# experimentboard.net
KiCad netlist of a schematic drawn in EAGLE
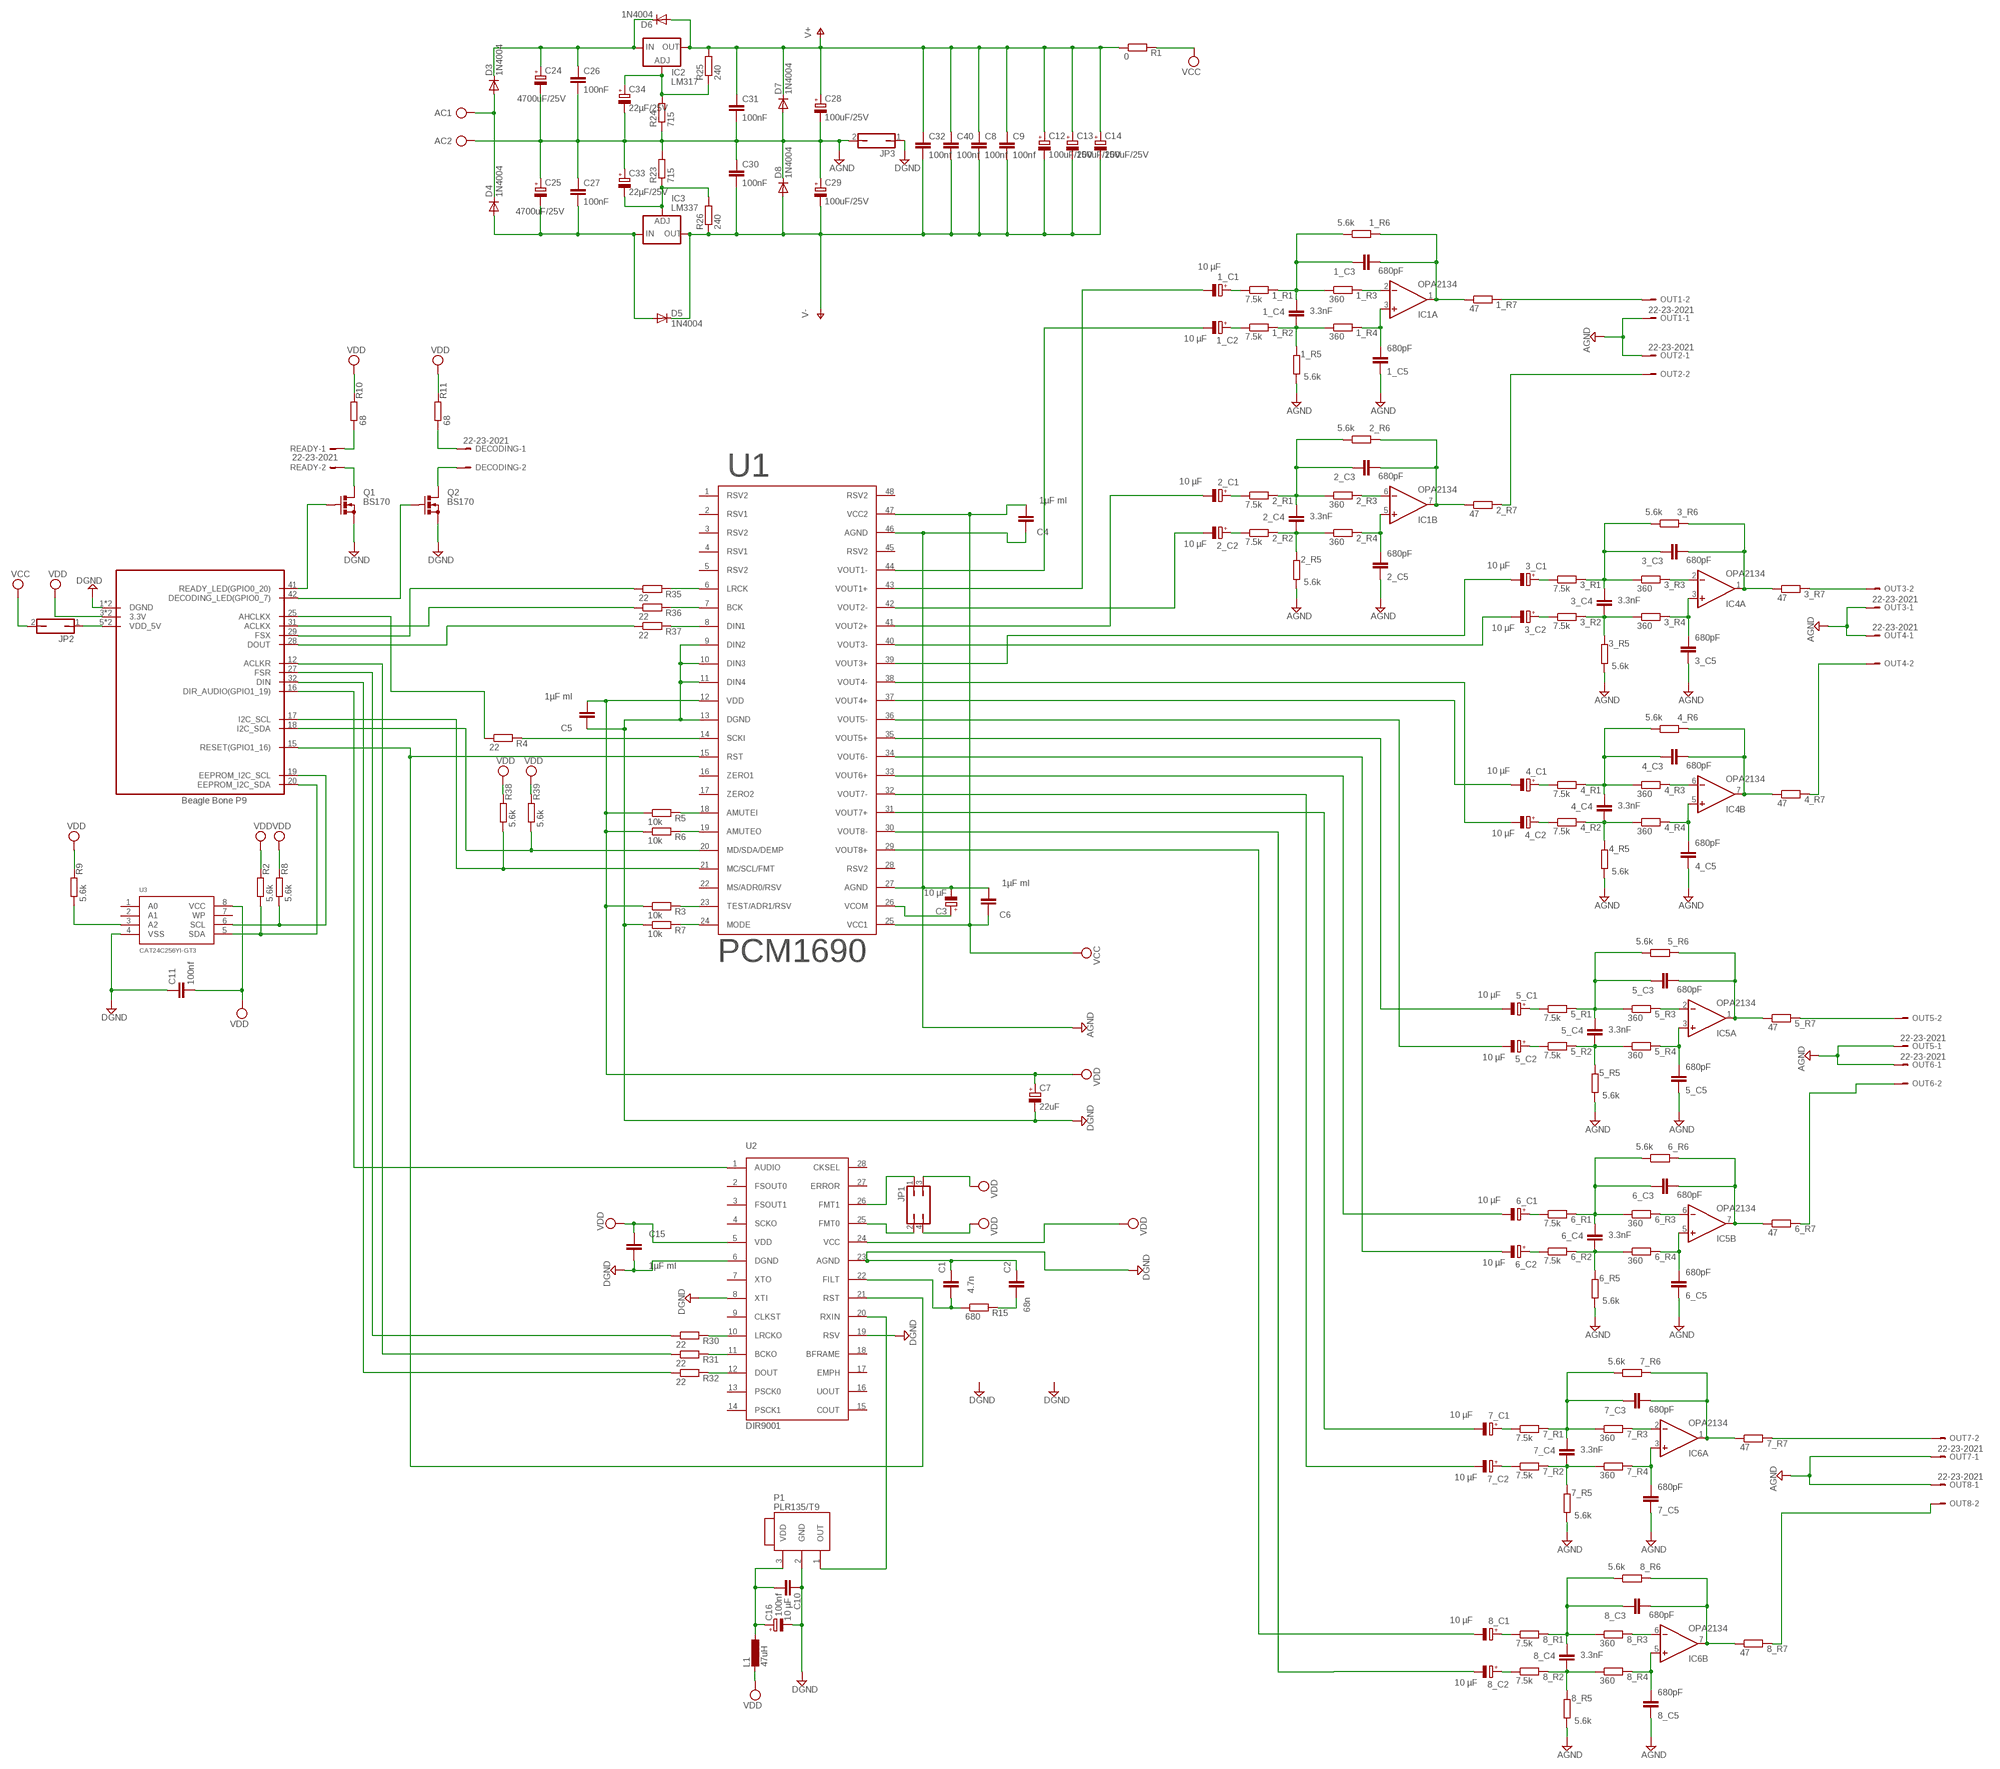
[diagram p0: schematic, sheet 1]

(export (version "E")
  (design (tool "Eeschema 10.0.6"))
  (components
    (comp (ref "1_C1")
      (value "10 µF")
      (footprint "eagle-import:E2-5")
      (libsource (lib "eagle-import") (part "CPOL-EUE2-5"))
    )
    (comp (ref "1_C2")
      (value "10 µF")
      (footprint "eagle-import:E2-5")
      (libsource (lib "eagle-import") (part "CPOL-EUE2-5"))
    )
    (comp (ref "1_C3")
      (value "680pF")
      (footprint "eagle-import:C050-024X044")
      (libsource (lib "eagle-import") (part "C-EU050-024X044"))
    )
    (comp (ref "1_C4")
      (value "3.3nF")
      (footprint "eagle-import:C050-025X075")
      (libsource (lib "eagle-import") (part "C-EU050-025X075"))
    )
    (comp (ref "1_C5")
      (value "680pF")
      (footprint "eagle-import:C050-024X044")
      (libsource (lib "eagle-import") (part "C-EU050-024X044"))
    )
    (comp (ref "1_R1")
      (value "7.5k")
      (footprint "eagle-import:0207_7")
      (libsource (lib "eagle-import") (part "R-EU_0207/7"))
    )
    (comp (ref "1_R2")
      (value "7.5k")
      (footprint "eagle-import:0207_7")
      (libsource (lib "eagle-import") (part "R-EU_0207/7"))
    )
    (comp (ref "1_R3")
      (value "360")
      (footprint "eagle-import:0207_7")
      (libsource (lib "eagle-import") (part "R-EU_0207/7"))
    )
    (comp (ref "1_R4")
      (value "360")
      (footprint "eagle-import:0207_7")
      (libsource (lib "eagle-import") (part "R-EU_0207/7"))
    )
    (comp (ref "1_R5")
      (value "5.6k")
      (footprint "eagle-import:0207_7")
      (libsource (lib "eagle-import") (part "R-EU_0207/7"))
    )
    (comp (ref "1_R6")
      (value "5.6k")
      (footprint "eagle-import:0207_7")
      (libsource (lib "eagle-import") (part "R-EU_0207/7"))
    )
    (comp (ref "1_R7")
      (value "47")
      (footprint "eagle-import:0207_7")
      (libsource (lib "eagle-import") (part "R-EU_0207/7"))
    )
    (comp (ref "2_C1")
      (value "10 µF")
      (footprint "eagle-import:E2-5")
      (libsource (lib "eagle-import") (part "CPOL-EUE2-5"))
    )
    (comp (ref "2_C2")
      (value "10 µF")
      (footprint "eagle-import:E2-5")
      (libsource (lib "eagle-import") (part "CPOL-EUE2-5"))
    )
    (comp (ref "2_C3")
      (value "680pF")
      (footprint "eagle-import:C050-024X044")
      (libsource (lib "eagle-import") (part "C-EU050-024X044"))
    )
    (comp (ref "2_C4")
      (value "3.3nF")
      (footprint "eagle-import:C050-025X075")
      (libsource (lib "eagle-import") (part "C-EU050-025X075"))
    )
    (comp (ref "2_C5")
      (value "680pF")
      (footprint "eagle-import:C050-024X044")
      (libsource (lib "eagle-import") (part "C-EU050-024X044"))
    )
    (comp (ref "2_R1")
      (value "7.5k")
      (footprint "eagle-import:0207_7")
      (libsource (lib "eagle-import") (part "R-EU_0207/7"))
    )
    (comp (ref "2_R2")
      (value "7.5k")
      (footprint "eagle-import:0207_7")
      (libsource (lib "eagle-import") (part "R-EU_0207/7"))
    )
    (comp (ref "2_R3")
      (value "360")
      (footprint "eagle-import:0207_7")
      (libsource (lib "eagle-import") (part "R-EU_0207/7"))
    )
    (comp (ref "2_R4")
      (value "360")
      (footprint "eagle-import:0207_7")
      (libsource (lib "eagle-import") (part "R-EU_0207/7"))
    )
    (comp (ref "2_R5")
      (value "5.6k")
      (footprint "eagle-import:0207_7")
      (libsource (lib "eagle-import") (part "R-EU_0207/7"))
    )
    (comp (ref "2_R6")
      (value "5.6k")
      (footprint "eagle-import:0207_7")
      (libsource (lib "eagle-import") (part "R-EU_0207/7"))
    )
    (comp (ref "2_R7")
      (value "47")
      (footprint "eagle-import:0207_7")
      (libsource (lib "eagle-import") (part "R-EU_0207/7"))
    )
    (comp (ref "3_C1")
      (value "10 µF")
      (footprint "eagle-import:E2-5")
      (libsource (lib "eagle-import") (part "CPOL-EUE2-5"))
    )
    (comp (ref "3_C2")
      (value "10 µF")
      (footprint "eagle-import:E2-5")
      (libsource (lib "eagle-import") (part "CPOL-EUE2-5"))
    )
    (comp (ref "3_C3")
      (value "680pF")
      (footprint "eagle-import:C050-024X044")
      (libsource (lib "eagle-import") (part "C-EU050-024X044"))
    )
    (comp (ref "3_C4")
      (value "3.3nF")
      (footprint "eagle-import:C050-025X075")
      (libsource (lib "eagle-import") (part "C-EU050-025X075"))
    )
    (comp (ref "3_C5")
      (value "680pF")
      (footprint "eagle-import:C050-024X044")
      (libsource (lib "eagle-import") (part "C-EU050-024X044"))
    )
    (comp (ref "3_R1")
      (value "7.5k")
      (footprint "eagle-import:0207_7")
      (libsource (lib "eagle-import") (part "R-EU_0207/7"))
    )
    (comp (ref "3_R2")
      (value "7.5k")
      (footprint "eagle-import:0207_7")
      (libsource (lib "eagle-import") (part "R-EU_0207/7"))
    )
    (comp (ref "3_R3")
      (value "360")
      (footprint "eagle-import:0207_7")
      (libsource (lib "eagle-import") (part "R-EU_0207/7"))
    )
    (comp (ref "3_R4")
      (value "360")
      (footprint "eagle-import:0207_7")
      (libsource (lib "eagle-import") (part "R-EU_0207/7"))
    )
    (comp (ref "3_R5")
      (value "5.6k")
      (footprint "eagle-import:0207_7")
      (libsource (lib "eagle-import") (part "R-EU_0207/7"))
    )
    (comp (ref "3_R6")
      (value "5.6k")
      (footprint "eagle-import:0207_7")
      (libsource (lib "eagle-import") (part "R-EU_0207/7"))
    )
    (comp (ref "3_R7")
      (value "47")
      (footprint "eagle-import:0207_7")
      (libsource (lib "eagle-import") (part "R-EU_0207/7"))
    )
    (comp (ref "4_C1")
      (value "10 µF")
      (footprint "eagle-import:E2-5")
      (libsource (lib "eagle-import") (part "CPOL-EUE2-5"))
    )
    (comp (ref "4_C2")
      (value "10 µF")
      (footprint "eagle-import:E2-5")
      (libsource (lib "eagle-import") (part "CPOL-EUE2-5"))
    )
    (comp (ref "4_C3")
      (value "680pF")
      (footprint "eagle-import:C050-024X044")
      (libsource (lib "eagle-import") (part "C-EU050-024X044"))
    )
    (comp (ref "4_C4")
      (value "3.3nF")
      (footprint "eagle-import:C050-025X075")
      (libsource (lib "eagle-import") (part "C-EU050-025X075"))
    )
    (comp (ref "4_C5")
      (value "680pF")
      (footprint "eagle-import:C050-024X044")
      (libsource (lib "eagle-import") (part "C-EU050-024X044"))
    )
    (comp (ref "4_R1")
      (value "7.5k")
      (footprint "eagle-import:0207_7")
      (libsource (lib "eagle-import") (part "R-EU_0207/7"))
    )
    (comp (ref "4_R2")
      (value "7.5k")
      (footprint "eagle-import:0207_7")
      (libsource (lib "eagle-import") (part "R-EU_0207/7"))
    )
    (comp (ref "4_R3")
      (value "360")
      (footprint "eagle-import:0207_7")
      (libsource (lib "eagle-import") (part "R-EU_0207/7"))
    )
    (comp (ref "4_R4")
      (value "360")
      (footprint "eagle-import:0207_7")
      (libsource (lib "eagle-import") (part "R-EU_0207/7"))
    )
    (comp (ref "4_R5")
      (value "5.6k")
      (footprint "eagle-import:0207_7")
      (libsource (lib "eagle-import") (part "R-EU_0207/7"))
    )
    (comp (ref "4_R6")
      (value "5.6k")
      (footprint "eagle-import:0207_7")
      (libsource (lib "eagle-import") (part "R-EU_0207/7"))
    )
    (comp (ref "4_R7")
      (value "47")
      (footprint "eagle-import:0207_7")
      (libsource (lib "eagle-import") (part "R-EU_0207/7"))
    )
    (comp (ref "5_C1")
      (value "10 µF")
      (footprint "eagle-import:E2-5")
      (libsource (lib "eagle-import") (part "CPOL-EUE2-5"))
    )
    (comp (ref "5_C2")
      (value "10 µF")
      (footprint "eagle-import:E2-5")
      (libsource (lib "eagle-import") (part "CPOL-EUE2-5"))
    )
    (comp (ref "5_C3")
      (value "680pF")
      (footprint "eagle-import:C050-024X044")
      (libsource (lib "eagle-import") (part "C-EU050-024X044"))
    )
    (comp (ref "5_C4")
      (value "3.3nF")
      (footprint "eagle-import:C050-025X075")
      (libsource (lib "eagle-import") (part "C-EU050-025X075"))
    )
    (comp (ref "5_C5")
      (value "680pF")
      (footprint "eagle-import:C050-024X044")
      (libsource (lib "eagle-import") (part "C-EU050-024X044"))
    )
    (comp (ref "5_R1")
      (value "7.5k")
      (footprint "eagle-import:0207_7")
      (libsource (lib "eagle-import") (part "R-EU_0207/7"))
    )
    (comp (ref "5_R2")
      (value "7.5k")
      (footprint "eagle-import:0207_7")
      (libsource (lib "eagle-import") (part "R-EU_0207/7"))
    )
    (comp (ref "5_R3")
      (value "360")
      (footprint "eagle-import:0207_7")
      (libsource (lib "eagle-import") (part "R-EU_0207/7"))
    )
    (comp (ref "5_R4")
      (value "360")
      (footprint "eagle-import:0207_7")
      (libsource (lib "eagle-import") (part "R-EU_0207/7"))
    )
    (comp (ref "5_R5")
      (value "5.6k")
      (footprint "eagle-import:0207_7")
      (libsource (lib "eagle-import") (part "R-EU_0207/7"))
    )
    (comp (ref "5_R6")
      (value "5.6k")
      (footprint "eagle-import:0207_7")
      (libsource (lib "eagle-import") (part "R-EU_0207/7"))
    )
    (comp (ref "5_R7")
      (value "47")
      (footprint "eagle-import:0207_7")
      (libsource (lib "eagle-import") (part "R-EU_0207/7"))
    )
    (comp (ref "6_C1")
      (value "10 µF")
      (footprint "eagle-import:E2-5")
      (libsource (lib "eagle-import") (part "CPOL-EUE2-5"))
    )
    (comp (ref "6_C2")
      (value "10 µF")
      (footprint "eagle-import:E2-5")
      (libsource (lib "eagle-import") (part "CPOL-EUE2-5"))
    )
    (comp (ref "6_C3")
      (value "680pF")
      (footprint "eagle-import:C050-024X044")
      (libsource (lib "eagle-import") (part "C-EU050-024X044"))
    )
    (comp (ref "6_C4")
      (value "3.3nF")
      (footprint "eagle-import:C050-025X075")
      (libsource (lib "eagle-import") (part "C-EU050-025X075"))
    )
    (comp (ref "6_C5")
      (value "680pF")
      (footprint "eagle-import:C050-024X044")
      (libsource (lib "eagle-import") (part "C-EU050-024X044"))
    )
    (comp (ref "6_R1")
      (value "7.5k")
      (footprint "eagle-import:0207_7")
      (libsource (lib "eagle-import") (part "R-EU_0207/7"))
    )
    (comp (ref "6_R2")
      (value "7.5k")
      (footprint "eagle-import:0207_7")
      (libsource (lib "eagle-import") (part "R-EU_0207/7"))
    )
    (comp (ref "6_R3")
      (value "360")
      (footprint "eagle-import:0207_7")
      (libsource (lib "eagle-import") (part "R-EU_0207/7"))
    )
    (comp (ref "6_R4")
      (value "360")
      (footprint "eagle-import:0207_7")
      (libsource (lib "eagle-import") (part "R-EU_0207/7"))
    )
    (comp (ref "6_R5")
      (value "5.6k")
      (footprint "eagle-import:0207_7")
      (libsource (lib "eagle-import") (part "R-EU_0207/7"))
    )
    (comp (ref "6_R6")
      (value "5.6k")
      (footprint "eagle-import:0207_7")
      (libsource (lib "eagle-import") (part "R-EU_0207/7"))
    )
    (comp (ref "6_R7")
      (value "47")
      (footprint "eagle-import:0207_7")
      (libsource (lib "eagle-import") (part "R-EU_0207/7"))
    )
    (comp (ref "7_C1")
      (value "10 µF")
      (footprint "eagle-import:E2-5")
      (libsource (lib "eagle-import") (part "CPOL-EUE2-5"))
    )
    (comp (ref "7_C2")
      (value "10 µF")
      (footprint "eagle-import:E2-5")
      (libsource (lib "eagle-import") (part "CPOL-EUE2-5"))
    )
    (comp (ref "7_C3")
      (value "680pF")
      (footprint "eagle-import:C050-024X044")
      (libsource (lib "eagle-import") (part "C-EU050-024X044"))
    )
    (comp (ref "7_C4")
      (value "3.3nF")
      (footprint "eagle-import:C050-025X075")
      (libsource (lib "eagle-import") (part "C-EU050-025X075"))
    )
    (comp (ref "7_C5")
      (value "680pF")
      (footprint "eagle-import:C050-024X044")
      (libsource (lib "eagle-import") (part "C-EU050-024X044"))
    )
    (comp (ref "7_R1")
      (value "7.5k")
      (footprint "eagle-import:0207_7")
      (libsource (lib "eagle-import") (part "R-EU_0207/7"))
    )
    (comp (ref "7_R2")
      (value "7.5k")
      (footprint "eagle-import:0207_7")
      (libsource (lib "eagle-import") (part "R-EU_0207/7"))
    )
    (comp (ref "7_R3")
      (value "360")
      (footprint "eagle-import:0207_7")
      (libsource (lib "eagle-import") (part "R-EU_0207/7"))
    )
    (comp (ref "7_R4")
      (value "360")
      (footprint "eagle-import:0207_7")
      (libsource (lib "eagle-import") (part "R-EU_0207/7"))
    )
    (comp (ref "7_R5")
      (value "5.6k")
      (footprint "eagle-import:0207_7")
      (libsource (lib "eagle-import") (part "R-EU_0207/7"))
    )
    (comp (ref "7_R6")
      (value "5.6k")
      (footprint "eagle-import:0207_7")
      (libsource (lib "eagle-import") (part "R-EU_0207/7"))
    )
    (comp (ref "7_R7")
      (value "47")
      (footprint "eagle-import:0207_7")
      (libsource (lib "eagle-import") (part "R-EU_0207/7"))
    )
    (comp (ref "8_C1")
      (value "10 µF")
      (footprint "eagle-import:E2-5")
      (libsource (lib "eagle-import") (part "CPOL-EUE2-5"))
    )
    (comp (ref "8_C2")
      (value "10 µF")
      (footprint "eagle-import:E2-5")
      (libsource (lib "eagle-import") (part "CPOL-EUE2-5"))
    )
    (comp (ref "8_C3")
      (value "680pF")
      (footprint "eagle-import:C050-024X044")
      (libsource (lib "eagle-import") (part "C-EU050-024X044"))
    )
    (comp (ref "8_C4")
      (value "3.3nF")
      (footprint "eagle-import:C050-025X075")
      (libsource (lib "eagle-import") (part "C-EU050-025X075"))
    )
    (comp (ref "8_C5")
      (value "680pF")
      (footprint "eagle-import:C050-024X044")
      (libsource (lib "eagle-import") (part "C-EU050-024X044"))
    )
    (comp (ref "8_R1")
      (value "7.5k")
      (footprint "eagle-import:0207_7")
      (libsource (lib "eagle-import") (part "R-EU_0207/7"))
    )
    (comp (ref "8_R2")
      (value "7.5k")
      (footprint "eagle-import:0207_7")
      (libsource (lib "eagle-import") (part "R-EU_0207/7"))
    )
    (comp (ref "8_R3")
      (value "360")
      (footprint "eagle-import:0207_7")
      (libsource (lib "eagle-import") (part "R-EU_0207/7"))
    )
    (comp (ref "8_R4")
      (value "360")
      (footprint "eagle-import:0207_7")
      (libsource (lib "eagle-import") (part "R-EU_0207/7"))
    )
    (comp (ref "8_R5")
      (value "5.6k")
      (footprint "eagle-import:0207_7")
      (libsource (lib "eagle-import") (part "R-EU_0207/7"))
    )
    (comp (ref "8_R6")
      (value "5.6k")
      (footprint "eagle-import:0207_7")
      (libsource (lib "eagle-import") (part "R-EU_0207/7"))
    )
    (comp (ref "8_R7")
      (value "47")
      (footprint "eagle-import:0207_7")
      (libsource (lib "eagle-import") (part "R-EU_0207/7"))
    )
    (comp (ref "AC")
      (value "ADAPTER-PLUG-5.5MM")
      (footprint "eagle-import:ADAPTER-PLUG-5.5MM")
      (libsource (lib "eagle-import") (part "ADAPTER-PLUG-5.5MM"))
    )
    (comp (ref "C1")
      (value "4.7n")
      (footprint "eagle-import:C050-024X044")
      (libsource (lib "eagle-import") (part "C-EU050-024X044"))
    )
    (comp (ref "C2")
      (value "68n")
      (footprint "eagle-import:C050-024X044")
      (libsource (lib "eagle-import") (part "C-EU050-024X044"))
    )
    (comp (ref "C3")
      (value "10 µF")
      (footprint "eagle-import:E2-5")
      (libsource (lib "eagle-import") (part "CPOL-EUE2-5"))
    )
    (comp (ref "C4")
      (value "1µF ml")
      (footprint "eagle-import:C050-024X044")
      (libsource (lib "eagle-import") (part "C-EU050-024X044"))
    )
    (comp (ref "C5")
      (value "1µF ml")
      (footprint "eagle-import:C050-024X044")
      (libsource (lib "eagle-import") (part "C-EU050-024X044"))
    )
    (comp (ref "C6")
      (value "1µF ml")
      (footprint "eagle-import:C050-024X044")
      (libsource (lib "eagle-import") (part "C-EU050-024X044"))
    )
    (comp (ref "C7")
      (value "22uF")
      (footprint "eagle-import:E2-5")
      (libsource (lib "eagle-import") (part "CPOL-EUE2-5"))
    )
    (comp (ref "C8")
      (value "100nf")
      (footprint "eagle-import:C050-024X044")
      (libsource (lib "eagle-import") (part "C-EU050-024X044"))
    )
    (comp (ref "C9")
      (value "100nf")
      (footprint "eagle-import:C050-024X044")
      (libsource (lib "eagle-import") (part "C-EU050-024X044"))
    )
    (comp (ref "C10")
      (value "100nf")
      (footprint "eagle-import:C050-024X044")
      (libsource (lib "eagle-import") (part "C-EU050-024X044"))
    )
    (comp (ref "C11")
      (value "100nf")
      (footprint "eagle-import:C050-024X044")
      (libsource (lib "eagle-import") (part "C-EU050-024X044"))
    )
    (comp (ref "C12")
      (value "100uF/25V")
      (footprint "eagle-import:E2,5-6")
      (libsource (lib "eagle-import") (part "CPOL-EUE2.5-6"))
    )
    (comp (ref "C13")
      (value "100uF/25V")
      (footprint "eagle-import:E2,5-6")
      (libsource (lib "eagle-import") (part "CPOL-EUE2.5-6"))
    )
    (comp (ref "C14")
      (value "100uF/25V")
      (footprint "eagle-import:E2,5-6")
      (libsource (lib "eagle-import") (part "CPOL-EUE2.5-6"))
    )
    (comp (ref "C15")
      (value "1µF ml")
      (footprint "eagle-import:C050-024X044")
      (libsource (lib "eagle-import") (part "C-EU050-024X044"))
    )
    (comp (ref "C16")
      (value "10 µF")
      (footprint "eagle-import:E2-5")
      (libsource (lib "eagle-import") (part "CPOL-EUE2-5"))
    )
    (comp (ref "C24")
      (value "4700uF/25V")
      (footprint "eagle-import:E7,5-16")
      (libsource (lib "eagle-import") (part "CPOL-EUE7.5-16"))
    )
    (comp (ref "C25")
      (value "4700uF/25V")
      (footprint "eagle-import:E7,5-16")
      (libsource (lib "eagle-import") (part "CPOL-EUE7.5-16"))
    )
    (comp (ref "C26")
      (value "100nF")
      (footprint "eagle-import:C050-024X044")
      (libsource (lib "eagle-import") (part "C-EU050-024X044"))
    )
    (comp (ref "C27")
      (value "100nF")
      (footprint "eagle-import:C050-024X044")
      (libsource (lib "eagle-import") (part "C-EU050-024X044"))
    )
    (comp (ref "C28")
      (value "100uF/25V")
      (footprint "eagle-import:E2,5-6")
      (libsource (lib "eagle-import") (part "CPOL-EUE2.5-6"))
    )
    (comp (ref "C29")
      (value "100uF/25V")
      (footprint "eagle-import:E2,5-6")
      (libsource (lib "eagle-import") (part "CPOL-EUE2.5-6"))
    )
    (comp (ref "C30")
      (value "100nF")
      (footprint "eagle-import:C050-024X044")
      (libsource (lib "eagle-import") (part "C-EU050-024X044"))
    )
    (comp (ref "C31")
      (value "100nF")
      (footprint "eagle-import:C050-024X044")
      (libsource (lib "eagle-import") (part "C-EU050-024X044"))
    )
    (comp (ref "C32")
      (value "100nf")
      (footprint "eagle-import:C050-024X044")
      (libsource (lib "eagle-import") (part "C-EU050-024X044"))
    )
    (comp (ref "C33")
      (value "22µF/25V")
      (footprint "eagle-import:E2,5-6")
      (libsource (lib "eagle-import") (part "CPOL-EUE2.5-6"))
    )
    (comp (ref "C34")
      (value "22µF/25V")
      (footprint "eagle-import:E2,5-6")
      (libsource (lib "eagle-import") (part "CPOL-EUE2.5-6"))
    )
    (comp (ref "C40")
      (value "100nf")
      (footprint "eagle-import:C050-024X044")
      (libsource (lib "eagle-import") (part "C-EU050-024X044"))
    )
    (comp (ref "D3")
      (value "1N4004")
      (footprint "eagle-import:DO41-7.6")
      (libsource (lib "eagle-import") (part "DIODE-DO41-7.6"))
    )
    (comp (ref "D4")
      (value "1N4004")
      (footprint "eagle-import:DO41-7.6")
      (libsource (lib "eagle-import") (part "DIODE-DO41-7.6"))
    )
    (comp (ref "D5")
      (value "1N4004")
      (footprint "eagle-import:DO41-7.6")
      (libsource (lib "eagle-import") (part "DIODE-DO41-7.6"))
    )
    (comp (ref "D6")
      (value "1N4004")
      (footprint "eagle-import:DO41-7.6")
      (libsource (lib "eagle-import") (part "DIODE-DO41-7.6"))
    )
    (comp (ref "D7")
      (value "1N4004")
      (footprint "eagle-import:DO41-7.6")
      (libsource (lib "eagle-import") (part "DIODE-DO41-7.6"))
    )
    (comp (ref "D8")
      (value "1N4004")
      (footprint "eagle-import:DO41-7.6")
      (libsource (lib "eagle-import") (part "DIODE-DO41-7.6"))
    )
    (comp (ref "DECODING")
      (value "22-23-2021")
      (footprint "eagle-import:22-23-2021")
      (fields (field (name "MF") "MOLEX"))
      (libsource (lib "eagle-import") (part "22-23-2021"))
    )
    (comp (ref "IC1")
      (value "OPA2134")
      (footprint "eagle-import:DIL8")
      (libsource (lib "eagle-import") (part "TL072P"))
    )
    (comp (ref "IC2")
      (value "LM317")
      (footprint "eagle-import:317TS")
      (libsource (lib "eagle-import") (part "LM317TS"))
    )
    (comp (ref "IC3")
      (value "LM337")
      (footprint "eagle-import:337TS")
      (libsource (lib "eagle-import") (part "LM337TS"))
    )
    (comp (ref "IC4")
      (value "OPA2134")
      (footprint "eagle-import:DIL8")
      (libsource (lib "eagle-import") (part "TL072P"))
    )
    (comp (ref "IC5")
      (value "OPA2134")
      (footprint "eagle-import:DIL8")
      (libsource (lib "eagle-import") (part "TL072P"))
    )
    (comp (ref "IC6")
      (value "OPA2134")
      (footprint "eagle-import:DIL8")
      (libsource (lib "eagle-import") (part "TL072P"))
    )
    (comp (ref "JP1")
      (value "JP2Q")
      (footprint "eagle-import:JP2Q")
      (libsource (lib "eagle-import") (part "JP2Q"))
    )
    (comp (ref "JP2")
      (value "JP1Q")
      (footprint "eagle-import:JP1")
      (libsource (lib "eagle-import") (part "JP1Q"))
    )
    (comp (ref "JP3")
      (value "JP1Q")
      (footprint "eagle-import:JP1")
      (libsource (lib "eagle-import") (part "JP1Q"))
    )
    (comp (ref "L1")
      (value "47uH")
      (footprint "eagle-import:0207_10")
      (libsource (lib "eagle-import") (part "L-EU0207/10"))
    )
    (comp (ref "OUT1")
      (value "22-23-2021")
      (footprint "eagle-import:22-23-2021")
      (fields (field (name "MF") "MOLEX"))
      (libsource (lib "eagle-import") (part "22-23-2021"))
    )
    (comp (ref "OUT2")
      (value "22-23-2021")
      (footprint "eagle-import:22-23-2021")
      (fields (field (name "MF") "MOLEX"))
      (libsource (lib "eagle-import") (part "22-23-2021"))
    )
    (comp (ref "OUT3")
      (value "22-23-2021")
      (footprint "eagle-import:22-23-2021")
      (fields (field (name "MF") "MOLEX"))
      (libsource (lib "eagle-import") (part "22-23-2021"))
    )
    (comp (ref "OUT4")
      (value "22-23-2021")
      (footprint "eagle-import:22-23-2021")
      (fields (field (name "MF") "MOLEX"))
      (libsource (lib "eagle-import") (part "22-23-2021"))
    )
    (comp (ref "OUT5")
      (value "22-23-2021")
      (footprint "eagle-import:22-23-2021")
      (fields (field (name "MF") "MOLEX"))
      (libsource (lib "eagle-import") (part "22-23-2021"))
    )
    (comp (ref "OUT6")
      (value "22-23-2021")
      (footprint "eagle-import:22-23-2021")
      (fields (field (name "MF") "MOLEX"))
      (libsource (lib "eagle-import") (part "22-23-2021"))
    )
    (comp (ref "OUT7")
      (value "22-23-2021")
      (footprint "eagle-import:22-23-2021")
      (fields (field (name "MF") "MOLEX"))
      (libsource (lib "eagle-import") (part "22-23-2021"))
    )
    (comp (ref "OUT8")
      (value "22-23-2021")
      (footprint "eagle-import:22-23-2021")
      (fields (field (name "MF") "MOLEX"))
      (libsource (lib "eagle-import") (part "22-23-2021"))
    )
    (comp (ref "P1")
      (value "PLR135/T9")
      (footprint "eagle-import:PLR135_T9")
      (libsource (lib "eagle-import") (part "PLR135/T9"))
    )
    (comp (ref "P9")
      (value "P9")
      (footprint "eagle-import:HEADERS23-2")
      (libsource (lib "eagle-import") (part "BEAGLEBONEP9"))
    )
    (comp (ref "Q1")
      (value "BS170")
      (footprint "eagle-import:SOT54E")
      (libsource (lib "eagle-import") (part "BS170"))
    )
    (comp (ref "Q2")
      (value "BS170")
      (footprint "eagle-import:SOT54E")
      (libsource (lib "eagle-import") (part "BS170"))
    )
    (comp (ref "R1")
      (value "0")
      (footprint "eagle-import:0204V")
      (libsource (lib "eagle-import") (part "R-EU_0204/2V"))
    )
    (comp (ref "R2")
      (value "5.6k")
      (footprint "eagle-import:0207_7")
      (libsource (lib "eagle-import") (part "R-EU_0207/7"))
    )
    (comp (ref "R3")
      (value "10k")
      (footprint "eagle-import:0207_7")
      (libsource (lib "eagle-import") (part "R-EU_0207/7"))
    )
    (comp (ref "R4")
      (value "22")
      (footprint "eagle-import:0207_7")
      (libsource (lib "eagle-import") (part "R-EU_0207/7"))
    )
    (comp (ref "R5")
      (value "10k")
      (footprint "eagle-import:0207_7")
      (libsource (lib "eagle-import") (part "R-EU_0207/7"))
    )
    (comp (ref "R6")
      (value "10k")
      (footprint "eagle-import:0207_7")
      (libsource (lib "eagle-import") (part "R-EU_0207/7"))
    )
    (comp (ref "R7")
      (value "10k")
      (footprint "eagle-import:0207_7")
      (libsource (lib "eagle-import") (part "R-EU_0207/7"))
    )
    (comp (ref "R8")
      (value "5.6k")
      (footprint "eagle-import:0207_7")
      (libsource (lib "eagle-import") (part "R-EU_0207/7"))
    )
    (comp (ref "R9")
      (value "5.6k")
      (footprint "eagle-import:0207_7")
      (libsource (lib "eagle-import") (part "R-EU_0207/7"))
    )
    (comp (ref "R10")
      (value "68")
      (footprint "eagle-import:0204V")
      (libsource (lib "eagle-import") (part "R-EU_0204/2V"))
    )
    (comp (ref "R11")
      (value "68")
      (footprint "eagle-import:0204V")
      (libsource (lib "eagle-import") (part "R-EU_0204/2V"))
    )
    (comp (ref "R15")
      (value "680")
      (footprint "eagle-import:0207_7")
      (libsource (lib "eagle-import") (part "R-EU_0207/7"))
    )
    (comp (ref "R23")
      (value "715")
      (footprint "eagle-import:0207_10")
      (libsource (lib "eagle-import") (part "R-EU_0207/10"))
    )
    (comp (ref "R24")
      (value "715")
      (footprint "eagle-import:0207_10")
      (libsource (lib "eagle-import") (part "R-EU_0207/10"))
    )
    (comp (ref "R25")
      (value "240")
      (footprint "eagle-import:0207_10")
      (libsource (lib "eagle-import") (part "R-EU_0207/10"))
    )
    (comp (ref "R26")
      (value "240")
      (footprint "eagle-import:0207_10")
      (libsource (lib "eagle-import") (part "R-EU_0207/10"))
    )
    (comp (ref "R30")
      (value "22")
      (footprint "eagle-import:0207_7")
      (libsource (lib "eagle-import") (part "R-EU_0207/7"))
    )
    (comp (ref "R31")
      (value "22")
      (footprint "eagle-import:0207_7")
      (libsource (lib "eagle-import") (part "R-EU_0207/7"))
    )
    (comp (ref "R32")
      (value "22")
      (footprint "eagle-import:0207_7")
      (libsource (lib "eagle-import") (part "R-EU_0207/7"))
    )
    (comp (ref "R35")
      (value "22")
      (footprint "eagle-import:0207_7")
      (libsource (lib "eagle-import") (part "R-EU_0207/7"))
    )
    (comp (ref "R36")
      (value "22")
      (footprint "eagle-import:0207_7")
      (libsource (lib "eagle-import") (part "R-EU_0207/7"))
    )
    (comp (ref "R37")
      (value "22")
      (footprint "eagle-import:0207_7")
      (libsource (lib "eagle-import") (part "R-EU_0207/7"))
    )
    (comp (ref "R38")
      (value "5.6k")
      (footprint "eagle-import:0207_7")
      (libsource (lib "eagle-import") (part "R-EU_0207/7"))
    )
    (comp (ref "R39")
      (value "5.6k")
      (footprint "eagle-import:0207_7")
      (libsource (lib "eagle-import") (part "R-EU_0207/7"))
    )
    (comp (ref "READY")
      (value "22-23-2021")
      (footprint "eagle-import:22-23-2021")
      (fields (field (name "MF") "MOLEX"))
      (libsource (lib "eagle-import") (part "22-23-2021"))
    )
    (comp (ref "U1")
      (value "PCM1690")
      (footprint "eagle-import:HTSSOP48DFD")
      (libsource (lib "eagle-import") (part "PCM1690"))
    )
    (comp (ref "U2")
      (value "DIR9001")
      (footprint "eagle-import:TSSOP28")
      (libsource (lib "eagle-import") (part "DIR9001"))
    )
    (comp (ref "U3")
      (value "CAT24C256YI-GT3")
      (footprint "eagle-import:TSSOP8")
      (libsource (lib "eagle-import") (part "CAT24C256YI-GT3"))
    )
  )
  (nets
    (net (code "1") (name "AGND") (class "Default")
      (node (ref "1_C5") (pin "1") (pinfunction "1_1") (pintype "passive"))
      (node (ref "1_R5") (pin "1") (pinfunction "1_1") (pintype "passive"))
      (node (ref "2_C5") (pin "1") (pinfunction "1_1") (pintype "passive"))
      (node (ref "2_R5") (pin "1") (pinfunction "1_1") (pintype "passive"))
      (node (ref "3_C5") (pin "1") (pinfunction "1_1") (pintype "passive"))
      (node (ref "3_R5") (pin "1") (pinfunction "1_1") (pintype "passive"))
      (node (ref "4_C5") (pin "1") (pinfunction "1_1") (pintype "passive"))
      (node (ref "4_R5") (pin "1") (pinfunction "1_1") (pintype "passive"))
      (node (ref "5_C5") (pin "1") (pinfunction "1_1") (pintype "passive"))
      (node (ref "5_R5") (pin "1") (pinfunction "1_1") (pintype "passive"))
      (node (ref "6_C5") (pin "1") (pinfunction "1_1") (pintype "passive"))
      (node (ref "6_R5") (pin "1") (pinfunction "1_1") (pintype "passive"))
      (node (ref "7_C5") (pin "1") (pinfunction "1_1") (pintype "passive"))
      (node (ref "7_R5") (pin "1") (pinfunction "1_1") (pintype "passive"))
      (node (ref "8_C5") (pin "1") (pinfunction "1_1") (pintype "passive"))
      (node (ref "8_R5") (pin "1") (pinfunction "1_1") (pintype "passive"))
      (node (ref "AC") (pin "3") (pinfunction "KL_3") (pintype "passive"))
      (node (ref "C24") (pin "-") (pinfunction "-_-") (pintype "passive"))
      (node (ref "C25") (pin "+") (pinfunction "+_+") (pintype "passive"))
      (node (ref "C26") (pin "2") (pinfunction "2_2") (pintype "passive"))
      (node (ref "C27") (pin "1") (pinfunction "1_1") (pintype "passive"))
      (node (ref "C28") (pin "-") (pinfunction "-_-") (pintype "passive"))
      (node (ref "C29") (pin "+") (pinfunction "+_+") (pintype "passive"))
      (node (ref "C3") (pin "-") (pinfunction "-_-") (pintype "passive"))
      (node (ref "C30") (pin "1") (pinfunction "1_1") (pintype "passive"))
      (node (ref "C31") (pin "2") (pinfunction "2_2") (pintype "passive"))
      (node (ref "C33") (pin "+") (pinfunction "+_+") (pintype "passive"))
      (node (ref "C34") (pin "-") (pinfunction "-_-") (pintype "passive"))
      (node (ref "C4") (pin "1") (pinfunction "1_1") (pintype "passive"))
      (node (ref "C6") (pin "2") (pinfunction "2_2") (pintype "passive"))
      (node (ref "D7") (pin "A") (pinfunction "A_A") (pintype "passive"))
      (node (ref "D8") (pin "C") (pinfunction "C_C") (pintype "passive"))
      (node (ref "JP3") (pin "2") (pinfunction "2_2") (pintype "passive"))
      (node (ref "OUT1") (pin "1") (pinfunction "S_1") (pintype "passive"))
      (node (ref "OUT2") (pin "1") (pinfunction "S_1") (pintype "passive"))
      (node (ref "OUT3") (pin "1") (pinfunction "S_1") (pintype "passive"))
      (node (ref "OUT4") (pin "1") (pinfunction "S_1") (pintype "passive"))
      (node (ref "OUT5") (pin "1") (pinfunction "S_1") (pintype "passive"))
      (node (ref "OUT6") (pin "1") (pinfunction "S_1") (pintype "passive"))
      (node (ref "OUT7") (pin "1") (pinfunction "S_1") (pintype "passive"))
      (node (ref "OUT8") (pin "1") (pinfunction "S_1") (pintype "passive"))
      (node (ref "R23") (pin "2") (pinfunction "2_2") (pintype "passive"))
      (node (ref "R24") (pin "1") (pinfunction "1_1") (pintype "passive"))
      (node (ref "U1") (pin "27") (pinfunction "AGND_27") (pintype "power_in"))
      (node (ref "U1") (pin "46") (pinfunction "AGND_46") (pintype "power_in"))
    )
    (net (code "2") (name "DGND") (class "Default")
      (node (ref "C1") (pin "1") (pinfunction "1_1") (pintype "passive"))
      (node (ref "C10") (pin "1") (pinfunction "1_1") (pintype "passive"))
      (node (ref "C11") (pin "1") (pinfunction "1_1") (pintype "passive"))
      (node (ref "C15") (pin "2") (pinfunction "2_2") (pintype "passive"))
      (node (ref "C16") (pin "-") (pinfunction "-_-") (pintype "passive"))
      (node (ref "C2") (pin "1") (pinfunction "1_1") (pintype "passive"))
      (node (ref "C5") (pin "1") (pinfunction "1_1") (pintype "passive"))
      (node (ref "C7") (pin "-") (pinfunction "-_-") (pintype "passive"))
      (node (ref "JP3") (pin "1") (pinfunction "1_1") (pintype "passive"))
      (node (ref "P1") (pin "2") (pinfunction "GND_2") (pintype "power_in"))
      (node (ref "P9") (pin "1") (pinfunction "DGND_1") (pintype "power_in"))
      (node (ref "P9") (pin "2") (pinfunction "DGND_2") (pintype "power_in"))
      (node (ref "Q1") (pin "S") (pinfunction "S_S") (pintype "passive"))
      (node (ref "Q2") (pin "S") (pinfunction "S_S") (pintype "passive"))
      (node (ref "R7") (pin "1") (pinfunction "1_1") (pintype "passive"))
      (node (ref "U1") (pin "10") (pinfunction "DIN3_10") (pintype "input"))
      (node (ref "U1") (pin "11") (pinfunction "DIN4_11") (pintype "input"))
      (node (ref "U1") (pin "13") (pinfunction "DGND_13") (pintype "power_in"))
      (node (ref "U1") (pin "9") (pinfunction "DIN2_9") (pintype "input"))
      (node (ref "U2") (pin "19") (pinfunction "RSV_19") (pintype "bidirectional"))
      (node (ref "U2") (pin "23") (pinfunction "AGND_23") (pintype "power_in"))
      (node (ref "U2") (pin "6") (pinfunction "DGND_6") (pintype "power_in"))
      (node (ref "U2") (pin "8") (pinfunction "XTI_8") (pintype "input"))
      (node (ref "U3") (pin "4") (pinfunction "VSS_4") (pintype "power_in"))
    )
    (net (code "3") (name "Net-(1_C1-Pad+)") (class "Default")
      (node (ref "1_C1") (pin "+") (pinfunction "+_+") (pintype "passive"))
      (node (ref "1_R1") (pin "1") (pinfunction "1_1") (pintype "passive"))
    )
    (net (code "4") (name "Net-(1_C2-Pad+)") (class "Default")
      (node (ref "1_C2") (pin "+") (pinfunction "+_+") (pintype "passive"))
      (node (ref "1_R2") (pin "1") (pinfunction "1_1") (pintype "passive"))
    )
    (net (code "5") (name "Net-(1_C3-Pad1)") (class "Default")
      (node (ref "1_C3") (pin "1") (pinfunction "1_1") (pintype "passive"))
      (node (ref "1_C4") (pin "2") (pinfunction "2_2") (pintype "passive"))
      (node (ref "1_R1") (pin "2") (pinfunction "2_2") (pintype "passive"))
      (node (ref "1_R3") (pin "1") (pinfunction "1_1") (pintype "passive"))
      (node (ref "1_R6") (pin "1") (pinfunction "1_1") (pintype "passive"))
    )
    (net (code "6") (name "Net-(1_C4-Pad1)") (class "Default")
      (node (ref "1_C4") (pin "1") (pinfunction "1_1") (pintype "passive"))
      (node (ref "1_R2") (pin "2") (pinfunction "2_2") (pintype "passive"))
      (node (ref "1_R4") (pin "1") (pinfunction "1_1") (pintype "passive"))
      (node (ref "1_R5") (pin "2") (pinfunction "2_2") (pintype "passive"))
    )
    (net (code "7") (name "Net-(2_C1-Pad+)") (class "Default")
      (node (ref "2_C1") (pin "+") (pinfunction "+_+") (pintype "passive"))
      (node (ref "2_R1") (pin "1") (pinfunction "1_1") (pintype "passive"))
    )
    (net (code "8") (name "Net-(2_C2-Pad+)") (class "Default")
      (node (ref "2_C2") (pin "+") (pinfunction "+_+") (pintype "passive"))
      (node (ref "2_R2") (pin "1") (pinfunction "1_1") (pintype "passive"))
    )
    (net (code "9") (name "Net-(2_C3-Pad1)") (class "Default")
      (node (ref "2_C3") (pin "1") (pinfunction "1_1") (pintype "passive"))
      (node (ref "2_C4") (pin "2") (pinfunction "2_2") (pintype "passive"))
      (node (ref "2_R1") (pin "2") (pinfunction "2_2") (pintype "passive"))
      (node (ref "2_R3") (pin "1") (pinfunction "1_1") (pintype "passive"))
      (node (ref "2_R6") (pin "1") (pinfunction "1_1") (pintype "passive"))
    )
    (net (code "10") (name "Net-(2_C4-Pad1)") (class "Default")
      (node (ref "2_C4") (pin "1") (pinfunction "1_1") (pintype "passive"))
      (node (ref "2_R2") (pin "2") (pinfunction "2_2") (pintype "passive"))
      (node (ref "2_R4") (pin "1") (pinfunction "1_1") (pintype "passive"))
      (node (ref "2_R5") (pin "2") (pinfunction "2_2") (pintype "passive"))
    )
    (net (code "11") (name "Net-(3_C1-Pad+)") (class "Default")
      (node (ref "3_C1") (pin "+") (pinfunction "+_+") (pintype "passive"))
      (node (ref "3_R1") (pin "1") (pinfunction "1_1") (pintype "passive"))
    )
    (net (code "12") (name "Net-(3_C2-Pad+)") (class "Default")
      (node (ref "3_C2") (pin "+") (pinfunction "+_+") (pintype "passive"))
      (node (ref "3_R2") (pin "1") (pinfunction "1_1") (pintype "passive"))
    )
    (net (code "13") (name "Net-(3_C3-Pad1)") (class "Default")
      (node (ref "3_C3") (pin "1") (pinfunction "1_1") (pintype "passive"))
      (node (ref "3_C4") (pin "2") (pinfunction "2_2") (pintype "passive"))
      (node (ref "3_R1") (pin "2") (pinfunction "2_2") (pintype "passive"))
      (node (ref "3_R3") (pin "1") (pinfunction "1_1") (pintype "passive"))
      (node (ref "3_R6") (pin "1") (pinfunction "1_1") (pintype "passive"))
    )
    (net (code "14") (name "Net-(3_C4-Pad1)") (class "Default")
      (node (ref "3_C4") (pin "1") (pinfunction "1_1") (pintype "passive"))
      (node (ref "3_R2") (pin "2") (pinfunction "2_2") (pintype "passive"))
      (node (ref "3_R4") (pin "1") (pinfunction "1_1") (pintype "passive"))
      (node (ref "3_R5") (pin "2") (pinfunction "2_2") (pintype "passive"))
    )
    (net (code "15") (name "Net-(4_C1-Pad+)") (class "Default")
      (node (ref "4_C1") (pin "+") (pinfunction "+_+") (pintype "passive"))
      (node (ref "4_R1") (pin "1") (pinfunction "1_1") (pintype "passive"))
    )
    (net (code "16") (name "Net-(4_C2-Pad+)") (class "Default")
      (node (ref "4_C2") (pin "+") (pinfunction "+_+") (pintype "passive"))
      (node (ref "4_R2") (pin "1") (pinfunction "1_1") (pintype "passive"))
    )
    (net (code "17") (name "Net-(4_C3-Pad1)") (class "Default")
      (node (ref "4_C3") (pin "1") (pinfunction "1_1") (pintype "passive"))
      (node (ref "4_C4") (pin "2") (pinfunction "2_2") (pintype "passive"))
      (node (ref "4_R1") (pin "2") (pinfunction "2_2") (pintype "passive"))
      (node (ref "4_R3") (pin "1") (pinfunction "1_1") (pintype "passive"))
      (node (ref "4_R6") (pin "1") (pinfunction "1_1") (pintype "passive"))
    )
    (net (code "18") (name "Net-(4_C4-Pad1)") (class "Default")
      (node (ref "4_C4") (pin "1") (pinfunction "1_1") (pintype "passive"))
      (node (ref "4_R2") (pin "2") (pinfunction "2_2") (pintype "passive"))
      (node (ref "4_R4") (pin "1") (pinfunction "1_1") (pintype "passive"))
      (node (ref "4_R5") (pin "2") (pinfunction "2_2") (pintype "passive"))
    )
    (net (code "19") (name "Net-(5_C1-Pad+)") (class "Default")
      (node (ref "5_C1") (pin "+") (pinfunction "+_+") (pintype "passive"))
      (node (ref "5_R1") (pin "1") (pinfunction "1_1") (pintype "passive"))
    )
    (net (code "20") (name "Net-(5_C2-Pad+)") (class "Default")
      (node (ref "5_C2") (pin "+") (pinfunction "+_+") (pintype "passive"))
      (node (ref "5_R2") (pin "1") (pinfunction "1_1") (pintype "passive"))
    )
    (net (code "21") (name "Net-(5_C3-Pad1)") (class "Default")
      (node (ref "5_C3") (pin "1") (pinfunction "1_1") (pintype "passive"))
      (node (ref "5_C4") (pin "2") (pinfunction "2_2") (pintype "passive"))
      (node (ref "5_R1") (pin "2") (pinfunction "2_2") (pintype "passive"))
      (node (ref "5_R3") (pin "1") (pinfunction "1_1") (pintype "passive"))
      (node (ref "5_R6") (pin "1") (pinfunction "1_1") (pintype "passive"))
    )
    (net (code "22") (name "Net-(5_C4-Pad1)") (class "Default")
      (node (ref "5_C4") (pin "1") (pinfunction "1_1") (pintype "passive"))
      (node (ref "5_R2") (pin "2") (pinfunction "2_2") (pintype "passive"))
      (node (ref "5_R4") (pin "1") (pinfunction "1_1") (pintype "passive"))
      (node (ref "5_R5") (pin "2") (pinfunction "2_2") (pintype "passive"))
    )
    (net (code "23") (name "Net-(6_C1-Pad+)") (class "Default")
      (node (ref "6_C1") (pin "+") (pinfunction "+_+") (pintype "passive"))
      (node (ref "6_R1") (pin "1") (pinfunction "1_1") (pintype "passive"))
    )
    (net (code "24") (name "Net-(6_C2-Pad+)") (class "Default")
      (node (ref "6_C2") (pin "+") (pinfunction "+_+") (pintype "passive"))
      (node (ref "6_R2") (pin "1") (pinfunction "1_1") (pintype "passive"))
    )
    (net (code "25") (name "Net-(6_C3-Pad1)") (class "Default")
      (node (ref "6_C3") (pin "1") (pinfunction "1_1") (pintype "passive"))
      (node (ref "6_C4") (pin "2") (pinfunction "2_2") (pintype "passive"))
      (node (ref "6_R1") (pin "2") (pinfunction "2_2") (pintype "passive"))
      (node (ref "6_R3") (pin "1") (pinfunction "1_1") (pintype "passive"))
      (node (ref "6_R6") (pin "1") (pinfunction "1_1") (pintype "passive"))
    )
    (net (code "26") (name "Net-(6_C4-Pad1)") (class "Default")
      (node (ref "6_C4") (pin "1") (pinfunction "1_1") (pintype "passive"))
      (node (ref "6_R2") (pin "2") (pinfunction "2_2") (pintype "passive"))
      (node (ref "6_R4") (pin "1") (pinfunction "1_1") (pintype "passive"))
      (node (ref "6_R5") (pin "2") (pinfunction "2_2") (pintype "passive"))
    )
    (net (code "27") (name "Net-(7_C1-Pad+)") (class "Default")
      (node (ref "7_C1") (pin "+") (pinfunction "+_+") (pintype "passive"))
      (node (ref "7_R1") (pin "1") (pinfunction "1_1") (pintype "passive"))
    )
    (net (code "28") (name "Net-(7_C2-Pad+)") (class "Default")
      (node (ref "7_C2") (pin "+") (pinfunction "+_+") (pintype "passive"))
      (node (ref "7_R2") (pin "1") (pinfunction "1_1") (pintype "passive"))
    )
    (net (code "29") (name "Net-(7_C3-Pad1)") (class "Default")
      (node (ref "7_C3") (pin "1") (pinfunction "1_1") (pintype "passive"))
      (node (ref "7_C4") (pin "2") (pinfunction "2_2") (pintype "passive"))
      (node (ref "7_R1") (pin "2") (pinfunction "2_2") (pintype "passive"))
      (node (ref "7_R3") (pin "1") (pinfunction "1_1") (pintype "passive"))
      (node (ref "7_R6") (pin "1") (pinfunction "1_1") (pintype "passive"))
    )
    (net (code "30") (name "Net-(7_C4-Pad1)") (class "Default")
      (node (ref "7_C4") (pin "1") (pinfunction "1_1") (pintype "passive"))
      (node (ref "7_R2") (pin "2") (pinfunction "2_2") (pintype "passive"))
      (node (ref "7_R4") (pin "1") (pinfunction "1_1") (pintype "passive"))
      (node (ref "7_R5") (pin "2") (pinfunction "2_2") (pintype "passive"))
    )
    (net (code "31") (name "Net-(8_C1-Pad+)") (class "Default")
      (node (ref "8_C1") (pin "+") (pinfunction "+_+") (pintype "passive"))
      (node (ref "8_R1") (pin "1") (pinfunction "1_1") (pintype "passive"))
    )
    (net (code "32") (name "Net-(8_C2-Pad+)") (class "Default")
      (node (ref "8_C2") (pin "+") (pinfunction "+_+") (pintype "passive"))
      (node (ref "8_R2") (pin "1") (pinfunction "1_1") (pintype "passive"))
    )
    (net (code "33") (name "Net-(8_C3-Pad1)") (class "Default")
      (node (ref "8_C3") (pin "1") (pinfunction "1_1") (pintype "passive"))
      (node (ref "8_C4") (pin "2") (pinfunction "2_2") (pintype "passive"))
      (node (ref "8_R1") (pin "2") (pinfunction "2_2") (pintype "passive"))
      (node (ref "8_R3") (pin "1") (pinfunction "1_1") (pintype "passive"))
      (node (ref "8_R6") (pin "1") (pinfunction "1_1") (pintype "passive"))
    )
    (net (code "34") (name "Net-(8_C4-Pad1)") (class "Default")
      (node (ref "8_C4") (pin "1") (pinfunction "1_1") (pintype "passive"))
      (node (ref "8_R2") (pin "2") (pinfunction "2_2") (pintype "passive"))
      (node (ref "8_R4") (pin "1") (pinfunction "1_1") (pintype "passive"))
      (node (ref "8_R5") (pin "2") (pinfunction "2_2") (pintype "passive"))
    )
    (net (code "35") (name "Net-(ACA-KL)") (class "Default")
      (node (ref "AC") (pin "1") (pinfunction "KL_1") (pintype "passive"))
      (node (ref "D3") (pin "A") (pinfunction "A_A") (pintype "passive"))
      (node (ref "D4") (pin "C") (pinfunction "C_C") (pintype "passive"))
    )
    (net (code "36") (name "Net-(C2-Pad2)") (class "Default")
      (node (ref "C2") (pin "2") (pinfunction "2_2") (pintype "passive"))
      (node (ref "R15") (pin "2") (pinfunction "2_2") (pintype "passive"))
    )
    (net (code "37") (name "Net-(DECODINGA-S)") (class "Default")
      (node (ref "DECODING") (pin "1") (pinfunction "S_1") (pintype "passive"))
      (node (ref "R11") (pin "1") (pinfunction "1_1") (pintype "passive"))
    )
    (net (code "38") (name "Net-(DECODINGB-S)") (class "Default")
      (node (ref "DECODING") (pin "2") (pinfunction "S_2") (pintype "passive"))
      (node (ref "Q2") (pin "D") (pinfunction "D_D") (pintype "passive"))
    )
    (net (code "39") (name "Net-(IC1A-+IN)") (class "Default")
      (node (ref "1_C5") (pin "2") (pinfunction "2_2") (pintype "passive"))
      (node (ref "1_R4") (pin "2") (pinfunction "2_2") (pintype "passive"))
      (node (ref "IC1") (pin "3") (pinfunction "+IN_3") (pintype "input"))
    )
    (net (code "40") (name "Net-(IC1A--IN)") (class "Default")
      (node (ref "1_R3") (pin "2") (pinfunction "2_2") (pintype "passive"))
      (node (ref "IC1") (pin "2") (pinfunction "-IN_2") (pintype "input"))
    )
    (net (code "41") (name "Net-(IC1A-OUT)") (class "Default")
      (node (ref "1_C3") (pin "2") (pinfunction "2_2") (pintype "passive"))
      (node (ref "1_R6") (pin "2") (pinfunction "2_2") (pintype "passive"))
      (node (ref "1_R7") (pin "1") (pinfunction "1_1") (pintype "passive"))
      (node (ref "IC1") (pin "1") (pinfunction "OUT_1") (pintype "output"))
    )
    (net (code "42") (name "Net-(IC1B-+IN)") (class "Default")
      (node (ref "2_C5") (pin "2") (pinfunction "2_2") (pintype "passive"))
      (node (ref "2_R4") (pin "2") (pinfunction "2_2") (pintype "passive"))
      (node (ref "IC1") (pin "5") (pinfunction "+IN_5") (pintype "input"))
    )
    (net (code "43") (name "Net-(IC1B--IN)") (class "Default")
      (node (ref "2_R3") (pin "2") (pinfunction "2_2") (pintype "passive"))
      (node (ref "IC1") (pin "6") (pinfunction "-IN_6") (pintype "input"))
    )
    (net (code "44") (name "Net-(IC1B-OUT)") (class "Default")
      (node (ref "2_C3") (pin "2") (pinfunction "2_2") (pintype "passive"))
      (node (ref "2_R6") (pin "2") (pinfunction "2_2") (pintype "passive"))
      (node (ref "2_R7") (pin "1") (pinfunction "1_1") (pintype "passive"))
      (node (ref "IC1") (pin "7") (pinfunction "OUT_7") (pintype "output"))
    )
    (net (code "45") (name "Net-(IC2-ADJ)") (class "Default")
      (node (ref "C34") (pin "+") (pinfunction "+_+") (pintype "passive"))
      (node (ref "IC2") (pin "1") (pinfunction "ADJ_1") (pintype "input"))
      (node (ref "R24") (pin "2") (pinfunction "2_2") (pintype "passive"))
      (node (ref "R25") (pin "1") (pinfunction "1_1") (pintype "passive"))
    )
    (net (code "46") (name "Net-(IC2-IN)") (class "Default")
      (node (ref "C24") (pin "+") (pinfunction "+_+") (pintype "passive"))
      (node (ref "C26") (pin "1") (pinfunction "1_1") (pintype "passive"))
      (node (ref "D3") (pin "C") (pinfunction "C_C") (pintype "passive"))
      (node (ref "D6") (pin "C") (pinfunction "C_C") (pintype "passive"))
      (node (ref "IC2") (pin "3") (pinfunction "IN_3") (pintype "input"))
    )
    (net (code "47") (name "Net-(IC3-ADJ)") (class "Default")
      (node (ref "C33") (pin "-") (pinfunction "-_-") (pintype "passive"))
      (node (ref "IC3") (pin "1") (pinfunction "ADJ_1") (pintype "input"))
      (node (ref "R23") (pin "1") (pinfunction "1_1") (pintype "passive"))
      (node (ref "R26") (pin "2") (pinfunction "2_2") (pintype "passive"))
    )
    (net (code "48") (name "Net-(IC3-IN)") (class "Default")
      (node (ref "C25") (pin "-") (pinfunction "-_-") (pintype "passive"))
      (node (ref "C27") (pin "2") (pinfunction "2_2") (pintype "passive"))
      (node (ref "D4") (pin "A") (pinfunction "A_A") (pintype "passive"))
      (node (ref "D5") (pin "A") (pinfunction "A_A") (pintype "passive"))
      (node (ref "IC3") (pin "2") (pinfunction "IN_2") (pintype "input"))
    )
    (net (code "49") (name "Net-(IC4A-+IN)") (class "Default")
      (node (ref "3_C5") (pin "2") (pinfunction "2_2") (pintype "passive"))
      (node (ref "3_R4") (pin "2") (pinfunction "2_2") (pintype "passive"))
      (node (ref "IC4") (pin "3") (pinfunction "+IN_3") (pintype "input"))
    )
    (net (code "50") (name "Net-(IC4A--IN)") (class "Default")
      (node (ref "3_R3") (pin "2") (pinfunction "2_2") (pintype "passive"))
      (node (ref "IC4") (pin "2") (pinfunction "-IN_2") (pintype "input"))
    )
    (net (code "51") (name "Net-(IC4A-OUT)") (class "Default")
      (node (ref "3_C3") (pin "2") (pinfunction "2_2") (pintype "passive"))
      (node (ref "3_R6") (pin "2") (pinfunction "2_2") (pintype "passive"))
      (node (ref "3_R7") (pin "1") (pinfunction "1_1") (pintype "passive"))
      (node (ref "IC4") (pin "1") (pinfunction "OUT_1") (pintype "output"))
    )
    (net (code "52") (name "Net-(IC4B-+IN)") (class "Default")
      (node (ref "4_C5") (pin "2") (pinfunction "2_2") (pintype "passive"))
      (node (ref "4_R4") (pin "2") (pinfunction "2_2") (pintype "passive"))
      (node (ref "IC4") (pin "5") (pinfunction "+IN_5") (pintype "input"))
    )
    (net (code "53") (name "Net-(IC4B--IN)") (class "Default")
      (node (ref "4_R3") (pin "2") (pinfunction "2_2") (pintype "passive"))
      (node (ref "IC4") (pin "6") (pinfunction "-IN_6") (pintype "input"))
    )
    (net (code "54") (name "Net-(IC4B-OUT)") (class "Default")
      (node (ref "4_C3") (pin "2") (pinfunction "2_2") (pintype "passive"))
      (node (ref "4_R6") (pin "2") (pinfunction "2_2") (pintype "passive"))
      (node (ref "4_R7") (pin "1") (pinfunction "1_1") (pintype "passive"))
      (node (ref "IC4") (pin "7") (pinfunction "OUT_7") (pintype "output"))
    )
    (net (code "55") (name "Net-(IC5A-+IN)") (class "Default")
      (node (ref "5_C5") (pin "2") (pinfunction "2_2") (pintype "passive"))
      (node (ref "5_R4") (pin "2") (pinfunction "2_2") (pintype "passive"))
      (node (ref "IC5") (pin "3") (pinfunction "+IN_3") (pintype "input"))
    )
    (net (code "56") (name "Net-(IC5A--IN)") (class "Default")
      (node (ref "5_R3") (pin "2") (pinfunction "2_2") (pintype "passive"))
      (node (ref "IC5") (pin "2") (pinfunction "-IN_2") (pintype "input"))
    )
    (net (code "57") (name "Net-(IC5A-OUT)") (class "Default")
      (node (ref "5_C3") (pin "2") (pinfunction "2_2") (pintype "passive"))
      (node (ref "5_R6") (pin "2") (pinfunction "2_2") (pintype "passive"))
      (node (ref "5_R7") (pin "1") (pinfunction "1_1") (pintype "passive"))
      (node (ref "IC5") (pin "1") (pinfunction "OUT_1") (pintype "output"))
    )
    (net (code "58") (name "Net-(IC5B-+IN)") (class "Default")
      (node (ref "6_C5") (pin "2") (pinfunction "2_2") (pintype "passive"))
      (node (ref "6_R4") (pin "2") (pinfunction "2_2") (pintype "passive"))
      (node (ref "IC5") (pin "5") (pinfunction "+IN_5") (pintype "input"))
    )
    (net (code "59") (name "Net-(IC5B--IN)") (class "Default")
      (node (ref "6_R3") (pin "2") (pinfunction "2_2") (pintype "passive"))
      (node (ref "IC5") (pin "6") (pinfunction "-IN_6") (pintype "input"))
    )
    (net (code "60") (name "Net-(IC5B-OUT)") (class "Default")
      (node (ref "6_C3") (pin "2") (pinfunction "2_2") (pintype "passive"))
      (node (ref "6_R6") (pin "2") (pinfunction "2_2") (pintype "passive"))
      (node (ref "6_R7") (pin "1") (pinfunction "1_1") (pintype "passive"))
      (node (ref "IC5") (pin "7") (pinfunction "OUT_7") (pintype "output"))
    )
    (net (code "61") (name "Net-(IC6A-+IN)") (class "Default")
      (node (ref "7_C5") (pin "2") (pinfunction "2_2") (pintype "passive"))
      (node (ref "7_R4") (pin "2") (pinfunction "2_2") (pintype "passive"))
      (node (ref "IC6") (pin "3") (pinfunction "+IN_3") (pintype "input"))
    )
    (net (code "62") (name "Net-(IC6A--IN)") (class "Default")
      (node (ref "7_R3") (pin "2") (pinfunction "2_2") (pintype "passive"))
      (node (ref "IC6") (pin "2") (pinfunction "-IN_2") (pintype "input"))
    )
    (net (code "63") (name "Net-(IC6A-OUT)") (class "Default")
      (node (ref "7_C3") (pin "2") (pinfunction "2_2") (pintype "passive"))
      (node (ref "7_R6") (pin "2") (pinfunction "2_2") (pintype "passive"))
      (node (ref "7_R7") (pin "1") (pinfunction "1_1") (pintype "passive"))
      (node (ref "IC6") (pin "1") (pinfunction "OUT_1") (pintype "output"))
    )
    (net (code "64") (name "Net-(IC6B-+IN)") (class "Default")
      (node (ref "8_C5") (pin "2") (pinfunction "2_2") (pintype "passive"))
      (node (ref "8_R4") (pin "2") (pinfunction "2_2") (pintype "passive"))
      (node (ref "IC6") (pin "5") (pinfunction "+IN_5") (pintype "input"))
    )
    (net (code "65") (name "Net-(IC6B--IN)") (class "Default")
      (node (ref "8_R3") (pin "2") (pinfunction "2_2") (pintype "passive"))
      (node (ref "IC6") (pin "6") (pinfunction "-IN_6") (pintype "input"))
    )
    (net (code "66") (name "Net-(IC6B-OUT)") (class "Default")
      (node (ref "8_C3") (pin "2") (pinfunction "2_2") (pintype "passive"))
      (node (ref "8_R6") (pin "2") (pinfunction "2_2") (pintype "passive"))
      (node (ref "8_R7") (pin "1") (pinfunction "1_1") (pintype "passive"))
      (node (ref "IC6") (pin "7") (pinfunction "OUT_7") (pintype "output"))
    )
    (net (code "67") (name "Net-(JP2-Pad1)") (class "Default")
      (node (ref "JP2") (pin "1") (pinfunction "1_1") (pintype "passive"))
      (node (ref "P9") (pin "5") (pinfunction "VDD_5V_5") (pintype "power_in"))
      (node (ref "P9") (pin "6") (pinfunction "VDD_5V_6") (pintype "power_in"))
    )
    (net (code "68") (name "Net-(OUT1B-S)") (class "Default")
      (node (ref "1_R7") (pin "2") (pinfunction "2_2") (pintype "passive"))
      (node (ref "OUT1") (pin "2") (pinfunction "S_2") (pintype "passive"))
    )
    (net (code "69") (name "Net-(OUT2B-S)") (class "Default")
      (node (ref "2_R7") (pin "2") (pinfunction "2_2") (pintype "passive"))
      (node (ref "OUT2") (pin "2") (pinfunction "S_2") (pintype "passive"))
    )
    (net (code "70") (name "Net-(OUT3B-S)") (class "Default")
      (node (ref "3_R7") (pin "2") (pinfunction "2_2") (pintype "passive"))
      (node (ref "OUT3") (pin "2") (pinfunction "S_2") (pintype "passive"))
    )
    (net (code "71") (name "Net-(OUT4B-S)") (class "Default")
      (node (ref "4_R7") (pin "2") (pinfunction "2_2") (pintype "passive"))
      (node (ref "OUT4") (pin "2") (pinfunction "S_2") (pintype "passive"))
    )
    (net (code "72") (name "Net-(OUT5B-S)") (class "Default")
      (node (ref "5_R7") (pin "2") (pinfunction "2_2") (pintype "passive"))
      (node (ref "OUT5") (pin "2") (pinfunction "S_2") (pintype "passive"))
    )
    (net (code "73") (name "Net-(OUT6B-S)") (class "Default")
      (node (ref "6_R7") (pin "2") (pinfunction "2_2") (pintype "passive"))
      (node (ref "OUT6") (pin "2") (pinfunction "S_2") (pintype "passive"))
    )
    (net (code "74") (name "Net-(OUT7B-S)") (class "Default")
      (node (ref "7_R7") (pin "2") (pinfunction "2_2") (pintype "passive"))
      (node (ref "OUT7") (pin "2") (pinfunction "S_2") (pintype "passive"))
    )
    (net (code "75") (name "Net-(OUT8B-S)") (class "Default")
      (node (ref "8_R7") (pin "2") (pinfunction "2_2") (pintype "passive"))
      (node (ref "OUT8") (pin "2") (pinfunction "S_2") (pintype "passive"))
    )
    (net (code "76") (name "Net-(P1-OUT)") (class "Default")
      (node (ref "P1") (pin "1") (pinfunction "OUT_1") (pintype "output"))
      (node (ref "U2") (pin "20") (pinfunction "RXIN_20") (pintype "input"))
    )
    (net (code "77") (name "Net-(P1-VDD)") (class "Default")
      (node (ref "C10") (pin "2") (pinfunction "2_2") (pintype "passive"))
      (node (ref "C16") (pin "+") (pinfunction "+_+") (pintype "passive"))
      (node (ref "L1") (pin "1") (pinfunction "1_1") (pintype "passive"))
      (node (ref "P1") (pin "3") (pinfunction "VDD_3") (pintype "power_in"))
    )
    (net (code "78") (name "Net-(P9-ACLKR)") (class "Default")
      (node (ref "P9") (pin "12") (pinfunction "ACLKR_12") (pintype "bidirectional"))
      (node (ref "R31") (pin "1") (pinfunction "1_1") (pintype "passive"))
    )
    (net (code "79") (name "Net-(P9-ACLKX)") (class "Default")
      (node (ref "P9") (pin "31") (pinfunction "ACLKX_31") (pintype "bidirectional"))
      (node (ref "R36") (pin "1") (pinfunction "1_1") (pintype "passive"))
    )
    (net (code "80") (name "Net-(P9-AHCLKX)") (class "Default")
      (node (ref "P9") (pin "25") (pinfunction "AHCLKX_25") (pintype "bidirectional"))
      (node (ref "R4") (pin "1") (pinfunction "1_1") (pintype "passive"))
    )
    (net (code "81") (name "Net-(P9-DECODING_LED(GPIO0_7))") (class "Default")
      (node (ref "P9") (pin "42") (pinfunction "DECODING_LED(GPIO0_7)_42") (pintype "output"))
      (node (ref "Q2") (pin "G") (pinfunction "G_G") (pintype "passive"))
    )
    (net (code "82") (name "Net-(P9-DIN)") (class "Default")
      (node (ref "P9") (pin "32") (pinfunction "DIN_32") (pintype "bidirectional"))
      (node (ref "R32") (pin "1") (pinfunction "1_1") (pintype "passive"))
    )
    (net (code "83") (name "Net-(P9-DIR_AUDIO(GPIO1_19))") (class "Default")
      (node (ref "P9") (pin "16") (pinfunction "DIR_AUDIO(GPIO1_19)_16") (pintype "input"))
      (node (ref "U2") (pin "1") (pinfunction "AUDIO_1") (pintype "output"))
    )
    (net (code "84") (name "Net-(P9-DOUT)") (class "Default")
      (node (ref "P9") (pin "28") (pinfunction "DOUT_28") (pintype "bidirectional"))
      (node (ref "R37") (pin "1") (pinfunction "1_1") (pintype "passive"))
    )
    (net (code "85") (name "Net-(P9-EEPROM_I2C_SCL)") (class "Default")
      (node (ref "P9") (pin "19") (pinfunction "EEPROM_I2C_SCL_19") (pintype "bidirectional"))
      (node (ref "R8") (pin "1") (pinfunction "1_1") (pintype "passive"))
      (node (ref "U3") (pin "6") (pinfunction "SCL_6") (pintype "bidirectional"))
    )
    (net (code "86") (name "Net-(P9-EEPROM_I2C_SDA)") (class "Default")
      (node (ref "P9") (pin "20") (pinfunction "EEPROM_I2C_SDA_20") (pintype "bidirectional"))
      (node (ref "R2") (pin "1") (pinfunction "1_1") (pintype "passive"))
      (node (ref "U3") (pin "5") (pinfunction "SDA_5") (pintype "bidirectional"))
    )
    (net (code "87") (name "Net-(P9-FSR)") (class "Default")
      (node (ref "P9") (pin "27") (pinfunction "FSR_27") (pintype "bidirectional"))
      (node (ref "R30") (pin "1") (pinfunction "1_1") (pintype "passive"))
    )
    (net (code "88") (name "Net-(P9-FSX)") (class "Default")
      (node (ref "P9") (pin "29") (pinfunction "FSX_29") (pintype "bidirectional"))
      (node (ref "R35") (pin "1") (pinfunction "1_1") (pintype "passive"))
    )
    (net (code "89") (name "Net-(P9-I2C_SCL)") (class "Default")
      (node (ref "P9") (pin "17") (pinfunction "I2C_SCL_17") (pintype "bidirectional"))
      (node (ref "R38") (pin "1") (pinfunction "1_1") (pintype "passive"))
      (node (ref "U1") (pin "21") (pinfunction "MC/SCL/FMT_21") (pintype "input"))
    )
    (net (code "90") (name "Net-(P9-I2C_SDA)") (class "Default")
      (node (ref "P9") (pin "18") (pinfunction "I2C_SDA_18") (pintype "bidirectional"))
      (node (ref "R39") (pin "1") (pinfunction "1_1") (pintype "passive"))
      (node (ref "U1") (pin "20") (pinfunction "MD/SDA/DEMP_20") (pintype "bidirectional"))
    )
    (net (code "91") (name "Net-(P9-READY_LED(GPIO0_20))") (class "Default")
      (node (ref "P9") (pin "41") (pinfunction "READY_LED(GPIO0_20)_41") (pintype "output"))
      (node (ref "Q1") (pin "G") (pinfunction "G_G") (pintype "passive"))
    )
    (net (code "92") (name "Net-(P9-RESET(GPIO1_16))") (class "Default")
      (node (ref "P9") (pin "15") (pinfunction "RESET(GPIO1_16)_15") (pintype "output"))
      (node (ref "U1") (pin "15") (pinfunction "RST_15") (pintype "input"))
      (node (ref "U2") (pin "21") (pinfunction "RST_21") (pintype "input"))
    )
    (net (code "93") (name "Net-(READYA-S)") (class "Default")
      (node (ref "R10") (pin "1") (pinfunction "1_1") (pintype "passive"))
      (node (ref "READY") (pin "1") (pinfunction "S_1") (pintype "passive"))
    )
    (net (code "94") (name "Net-(READYB-S)") (class "Default")
      (node (ref "Q1") (pin "D") (pinfunction "D_D") (pintype "passive"))
      (node (ref "READY") (pin "2") (pinfunction "S_2") (pintype "passive"))
    )
    (net (code "95") (name "Net-(U1-AMUTEI)") (class "Default")
      (node (ref "R5") (pin "2") (pinfunction "2_2") (pintype "passive"))
      (node (ref "U1") (pin "18") (pinfunction "AMUTEI_18") (pintype "input"))
    )
    (net (code "96") (name "Net-(U1-AMUTEO)") (class "Default")
      (node (ref "R6") (pin "2") (pinfunction "2_2") (pintype "passive"))
      (node (ref "U1") (pin "19") (pinfunction "AMUTEO_19") (pintype "output"))
    )
    (net (code "97") (name "Net-(U1-BCK)") (class "Default")
      (node (ref "R36") (pin "2") (pinfunction "2_2") (pintype "passive"))
      (node (ref "U1") (pin "7") (pinfunction "BCK_7") (pintype "input"))
    )
    (net (code "98") (name "Net-(U1-DIN1)") (class "Default")
      (node (ref "R37") (pin "2") (pinfunction "2_2") (pintype "passive"))
      (node (ref "U1") (pin "8") (pinfunction "DIN1_8") (pintype "input"))
    )
    (net (code "99") (name "Net-(U1-LRCK)") (class "Default")
      (node (ref "R35") (pin "2") (pinfunction "2_2") (pintype "passive"))
      (node (ref "U1") (pin "6") (pinfunction "LRCK_6") (pintype "input"))
    )
    (net (code "100") (name "Net-(U1-MODE)") (class "Default")
      (node (ref "R7") (pin "2") (pinfunction "2_2") (pintype "passive"))
      (node (ref "U1") (pin "24") (pinfunction "MODE_24") (pintype "input"))
    )
    (net (code "101") (name "Net-(U1-SCKI)") (class "Default")
      (node (ref "R4") (pin "2") (pinfunction "2_2") (pintype "passive"))
      (node (ref "U1") (pin "14") (pinfunction "SCKI_14") (pintype "input"))
    )
    (net (code "102") (name "Net-(U1-TEST{slash}ADR1{slash}RSV)") (class "Default")
      (node (ref "R3") (pin "2") (pinfunction "2_2") (pintype "passive"))
      (node (ref "U1") (pin "23") (pinfunction "TEST/ADR1/RSV_23") (pintype "bidirectional"))
    )
    (net (code "103") (name "Net-(U1-VCOM)") (class "Default")
      (node (ref "C3") (pin "+") (pinfunction "+_+") (pintype "passive"))
      (node (ref "U1") (pin "26") (pinfunction "VCOM_26") (pintype "power_in"))
    )
    (net (code "104") (name "Net-(U1-VOUT1+)") (class "Default")
      (node (ref "1_C1") (pin "-") (pinfunction "-_-") (pintype "passive"))
      (node (ref "U1") (pin "43") (pinfunction "VOUT1+_43") (pintype "output"))
    )
    (net (code "105") (name "Net-(U1-VOUT1-)") (class "Default")
      (node (ref "1_C2") (pin "-") (pinfunction "-_-") (pintype "passive"))
      (node (ref "U1") (pin "44") (pinfunction "VOUT1-_44") (pintype "output"))
    )
    (net (code "106") (name "Net-(U1-VOUT2+)") (class "Default")
      (node (ref "2_C1") (pin "-") (pinfunction "-_-") (pintype "passive"))
      (node (ref "U1") (pin "41") (pinfunction "VOUT2+_41") (pintype "output"))
    )
    (net (code "107") (name "Net-(U1-VOUT2-)") (class "Default")
      (node (ref "2_C2") (pin "-") (pinfunction "-_-") (pintype "passive"))
      (node (ref "U1") (pin "42") (pinfunction "VOUT2-_42") (pintype "output"))
    )
    (net (code "108") (name "Net-(U1-VOUT3+)") (class "Default")
      (node (ref "3_C1") (pin "-") (pinfunction "-_-") (pintype "passive"))
      (node (ref "U1") (pin "39") (pinfunction "VOUT3+_39") (pintype "output"))
    )
    (net (code "109") (name "Net-(U1-VOUT3-)") (class "Default")
      (node (ref "3_C2") (pin "-") (pinfunction "-_-") (pintype "passive"))
      (node (ref "U1") (pin "40") (pinfunction "VOUT3-_40") (pintype "output"))
    )
    (net (code "110") (name "Net-(U1-VOUT4+)") (class "Default")
      (node (ref "4_C1") (pin "-") (pinfunction "-_-") (pintype "passive"))
      (node (ref "U1") (pin "37") (pinfunction "VOUT4+_37") (pintype "output"))
    )
    (net (code "111") (name "Net-(U1-VOUT4-)") (class "Default")
      (node (ref "4_C2") (pin "-") (pinfunction "-_-") (pintype "passive"))
      (node (ref "U1") (pin "38") (pinfunction "VOUT4-_38") (pintype "output"))
    )
    (net (code "112") (name "Net-(U1-VOUT5+)") (class "Default")
      (node (ref "5_C1") (pin "-") (pinfunction "-_-") (pintype "passive"))
      (node (ref "U1") (pin "35") (pinfunction "VOUT5+_35") (pintype "output"))
    )
    (net (code "113") (name "Net-(U1-VOUT5-)") (class "Default")
      (node (ref "5_C2") (pin "-") (pinfunction "-_-") (pintype "passive"))
      (node (ref "U1") (pin "36") (pinfunction "VOUT5-_36") (pintype "output"))
    )
    (net (code "114") (name "Net-(U1-VOUT6+)") (class "Default")
      (node (ref "6_C1") (pin "-") (pinfunction "-_-") (pintype "passive"))
      (node (ref "U1") (pin "33") (pinfunction "VOUT6+_33") (pintype "output"))
    )
    (net (code "115") (name "Net-(U1-VOUT6-)") (class "Default")
      (node (ref "6_C2") (pin "-") (pinfunction "-_-") (pintype "passive"))
      (node (ref "U1") (pin "34") (pinfunction "VOUT6-_34") (pintype "output"))
    )
    (net (code "116") (name "Net-(U1-VOUT7+)") (class "Default")
      (node (ref "7_C1") (pin "-") (pinfunction "-_-") (pintype "passive"))
      (node (ref "U1") (pin "31") (pinfunction "VOUT7+_31") (pintype "output"))
    )
    (net (code "117") (name "Net-(U1-VOUT7-)") (class "Default")
      (node (ref "7_C2") (pin "-") (pinfunction "-_-") (pintype "passive"))
      (node (ref "U1") (pin "32") (pinfunction "VOUT7-_32") (pintype "output"))
    )
    (net (code "118") (name "Net-(U1-VOUT8+)") (class "Default")
      (node (ref "8_C1") (pin "-") (pinfunction "-_-") (pintype "passive"))
      (node (ref "U1") (pin "29") (pinfunction "VOUT8+_29") (pintype "output"))
    )
    (net (code "119") (name "Net-(U1-VOUT8-)") (class "Default")
      (node (ref "8_C2") (pin "-") (pinfunction "-_-") (pintype "passive"))
      (node (ref "U1") (pin "30") (pinfunction "VOUT8-_30") (pintype "output"))
    )
    (net (code "120") (name "Net-(U2-BCKO)") (class "Default")
      (node (ref "R31") (pin "2") (pinfunction "2_2") (pintype "passive"))
      (node (ref "U2") (pin "11") (pinfunction "BCKO_11") (pintype "output"))
    )
    (net (code "121") (name "Net-(U2-DOUT)") (class "Default")
      (node (ref "R32") (pin "2") (pinfunction "2_2") (pintype "passive"))
      (node (ref "U2") (pin "12") (pinfunction "DOUT_12") (pintype "output"))
    )
    (net (code "122") (name "Net-(U2-FILT)") (class "Default")
      (node (ref "C1") (pin "2") (pinfunction "2_2") (pintype "passive"))
      (node (ref "R15") (pin "1") (pinfunction "1_1") (pintype "passive"))
      (node (ref "U2") (pin "22") (pinfunction "FILT_22") (pintype "bidirectional"))
    )
    (net (code "123") (name "Net-(U2-FMT0)") (class "Default")
      (node (ref "JP1") (pin "2") (pinfunction "2_2") (pintype "passive"))
      (node (ref "U2") (pin "25") (pinfunction "FMT0_25") (pintype "input"))
    )
    (net (code "124") (name "Net-(U2-FMT1)") (class "Default")
      (node (ref "JP1") (pin "1") (pinfunction "1_1") (pintype "passive"))
      (node (ref "U2") (pin "26") (pinfunction "FMT1_26") (pintype "input"))
    )
    (net (code "125") (name "Net-(U2-LRCKO)") (class "Default")
      (node (ref "R30") (pin "2") (pinfunction "2_2") (pintype "passive"))
      (node (ref "U2") (pin "10") (pinfunction "LRCKO_10") (pintype "output"))
    )
    (net (code "126") (name "Net-(U3-A2)") (class "Default")
      (node (ref "R9") (pin "1") (pinfunction "1_1") (pintype "passive"))
      (node (ref "U3") (pin "3") (pinfunction "A2_3") (pintype "input"))
    )
    (net (code "127") (name "V+") (class "Default")
      (node (ref "C12") (pin "+") (pinfunction "+_+") (pintype "passive"))
      (node (ref "C13") (pin "+") (pinfunction "+_+") (pintype "passive"))
      (node (ref "C14") (pin "+") (pinfunction "+_+") (pintype "passive"))
      (node (ref "C28") (pin "+") (pinfunction "+_+") (pintype "passive"))
      (node (ref "C31") (pin "1") (pinfunction "1_1") (pintype "passive"))
      (node (ref "C32") (pin "1") (pinfunction "1_1") (pintype "passive"))
      (node (ref "C40") (pin "1") (pinfunction "1_1") (pintype "passive"))
      (node (ref "C8") (pin "1") (pinfunction "1_1") (pintype "passive"))
      (node (ref "C9") (pin "1") (pinfunction "1_1") (pintype "passive"))
      (node (ref "D6") (pin "A") (pinfunction "A_A") (pintype "passive"))
      (node (ref "D7") (pin "C") (pinfunction "C_C") (pintype "passive"))
      (node (ref "IC2") (pin "2") (pinfunction "OUT_2") (pintype "passive"))
      (node (ref "R1") (pin "1") (pinfunction "1_1") (pintype "passive"))
      (node (ref "R25") (pin "2") (pinfunction "2_2") (pintype "passive"))
    )
    (net (code "128") (name "V-") (class "Default")
      (node (ref "C12") (pin "-") (pinfunction "-_-") (pintype "passive"))
      (node (ref "C13") (pin "-") (pinfunction "-_-") (pintype "passive"))
      (node (ref "C14") (pin "-") (pinfunction "-_-") (pintype "passive"))
      (node (ref "C29") (pin "-") (pinfunction "-_-") (pintype "passive"))
      (node (ref "C30") (pin "2") (pinfunction "2_2") (pintype "passive"))
      (node (ref "C32") (pin "2") (pinfunction "2_2") (pintype "passive"))
      (node (ref "C40") (pin "2") (pinfunction "2_2") (pintype "passive"))
      (node (ref "C8") (pin "2") (pinfunction "2_2") (pintype "passive"))
      (node (ref "C9") (pin "2") (pinfunction "2_2") (pintype "passive"))
      (node (ref "D5") (pin "C") (pinfunction "C_C") (pintype "passive"))
      (node (ref "D8") (pin "A") (pinfunction "A_A") (pintype "passive"))
      (node (ref "IC3") (pin "3") (pinfunction "OUT_3") (pintype "passive"))
      (node (ref "R26") (pin "1") (pinfunction "1_1") (pintype "passive"))
    )
    (net (code "129") (name "VCC") (class "Default")
      (node (ref "C4") (pin "2") (pinfunction "2_2") (pintype "passive"))
      (node (ref "C6") (pin "1") (pinfunction "1_1") (pintype "passive"))
      (node (ref "JP2") (pin "2") (pinfunction "2_2") (pintype "passive"))
      (node (ref "R1") (pin "2") (pinfunction "2_2") (pintype "passive"))
      (node (ref "U1") (pin "25") (pinfunction "VCC1_25") (pintype "power_in"))
      (node (ref "U1") (pin "47") (pinfunction "VCC2_47") (pintype "power_in"))
    )
    (net (code "130") (name "VDD") (class "Default")
      (node (ref "C11") (pin "2") (pinfunction "2_2") (pintype "passive"))
      (node (ref "C15") (pin "1") (pinfunction "1_1") (pintype "passive"))
      (node (ref "C5") (pin "2") (pinfunction "2_2") (pintype "passive"))
      (node (ref "C7") (pin "+") (pinfunction "+_+") (pintype "passive"))
      (node (ref "JP1") (pin "3") (pinfunction "3_3") (pintype "passive"))
      (node (ref "JP1") (pin "4") (pinfunction "4_4") (pintype "passive"))
      (node (ref "L1") (pin "2") (pinfunction "2_2") (pintype "passive"))
      (node (ref "P9") (pin "3") (pinfunction "3.3V_3") (pintype "power_in"))
      (node (ref "P9") (pin "4") (pinfunction "3.3V_4") (pintype "power_in"))
      (node (ref "R10") (pin "2") (pinfunction "2_2") (pintype "passive"))
      (node (ref "R11") (pin "2") (pinfunction "2_2") (pintype "passive"))
      (node (ref "R2") (pin "2") (pinfunction "2_2") (pintype "passive"))
      (node (ref "R3") (pin "1") (pinfunction "1_1") (pintype "passive"))
      (node (ref "R38") (pin "2") (pinfunction "2_2") (pintype "passive"))
      (node (ref "R39") (pin "2") (pinfunction "2_2") (pintype "passive"))
      (node (ref "R5") (pin "1") (pinfunction "1_1") (pintype "passive"))
      (node (ref "R6") (pin "1") (pinfunction "1_1") (pintype "passive"))
      (node (ref "R8") (pin "2") (pinfunction "2_2") (pintype "passive"))
      (node (ref "R9") (pin "2") (pinfunction "2_2") (pintype "passive"))
      (node (ref "U1") (pin "12") (pinfunction "VDD_12") (pintype "power_in"))
      (node (ref "U2") (pin "24") (pinfunction "VCC_24") (pintype "power_in"))
      (node (ref "U2") (pin "5") (pinfunction "VDD_5") (pintype "power_in"))
      (node (ref "U3") (pin "8") (pinfunction "VCC_8") (pintype "power_in"))
    )
    (net (code "131") (name "unconnected-(U1-MS{slash}ADR0{slash}RSV-Pad22)") (class "Default")
      (node (ref "U1") (pin "22") (pinfunction "MS/ADR0/RSV_22") (pintype "input"))
    )
    (net (code "132") (name "unconnected-(U1-RSV1-Pad2)") (class "Default")
      (node (ref "U1") (pin "2") (pinfunction "RSV1_2") (pintype "bidirectional"))
    )
    (net (code "133") (name "unconnected-(U1-RSV1-Pad4)") (class "Default")
      (node (ref "U1") (pin "4") (pinfunction "RSV1_4") (pintype "bidirectional"))
    )
    (net (code "134") (name "unconnected-(U1-RSV2-Pad1)") (class "Default")
      (node (ref "U1") (pin "1") (pinfunction "RSV2_1") (pintype "bidirectional"))
    )
    (net (code "135") (name "unconnected-(U1-RSV2-Pad3)") (class "Default")
      (node (ref "U1") (pin "3") (pinfunction "RSV2_3") (pintype "bidirectional"))
    )
    (net (code "136") (name "unconnected-(U1-RSV2-Pad5)") (class "Default")
      (node (ref "U1") (pin "5") (pinfunction "RSV2_5") (pintype "bidirectional"))
    )
    (net (code "137") (name "unconnected-(U1-RSV2-Pad28)") (class "Default")
      (node (ref "U1") (pin "28") (pinfunction "RSV2_28") (pintype "bidirectional"))
    )
    (net (code "138") (name "unconnected-(U1-RSV2-Pad45)") (class "Default")
      (node (ref "U1") (pin "45") (pinfunction "RSV2_45") (pintype "bidirectional"))
    )
    (net (code "139") (name "unconnected-(U1-RSV2-Pad48)") (class "Default")
      (node (ref "U1") (pin "48") (pinfunction "RSV2_48") (pintype "bidirectional"))
    )
    (net (code "140") (name "unconnected-(U1-ZERO1-Pad16)") (class "Default")
      (node (ref "U1") (pin "16") (pinfunction "ZERO1_16") (pintype "output"))
    )
    (net (code "141") (name "unconnected-(U1-ZERO2-Pad17)") (class "Default")
      (node (ref "U1") (pin "17") (pinfunction "ZERO2_17") (pintype "output"))
    )
    (net (code "142") (name "unconnected-(U2-BFRAME-Pad18)") (class "Default")
      (node (ref "U2") (pin "18") (pinfunction "BFRAME_18") (pintype "bidirectional"))
    )
    (net (code "143") (name "unconnected-(U2-CKSEL-Pad28)") (class "Default")
      (node (ref "U2") (pin "28") (pinfunction "CKSEL_28") (pintype "input"))
    )
    (net (code "144") (name "unconnected-(U2-CLKST-Pad9)") (class "Default")
      (node (ref "U2") (pin "9") (pinfunction "CLKST_9") (pintype "output"))
    )
    (net (code "145") (name "unconnected-(U2-COUT-Pad15)") (class "Default")
      (node (ref "U2") (pin "15") (pinfunction "COUT_15") (pintype "output"))
    )
    (net (code "146") (name "unconnected-(U2-EMPH-Pad17)") (class "Default")
      (node (ref "U2") (pin "17") (pinfunction "EMPH_17") (pintype "output"))
    )
    (net (code "147") (name "unconnected-(U2-ERROR-Pad27)") (class "Default")
      (node (ref "U2") (pin "27") (pinfunction "ERROR_27") (pintype "output"))
    )
    (net (code "148") (name "unconnected-(U2-FSOUT0-Pad2)") (class "Default")
      (node (ref "U2") (pin "2") (pinfunction "FSOUT0_2") (pintype "output"))
    )
    (net (code "149") (name "unconnected-(U2-FSOUT1-Pad3)") (class "Default")
      (node (ref "U2") (pin "3") (pinfunction "FSOUT1_3") (pintype "output"))
    )
    (net (code "150") (name "unconnected-(U2-PSCK0-Pad13)") (class "Default")
      (node (ref "U2") (pin "13") (pinfunction "PSCK0_13") (pintype "input"))
    )
    (net (code "151") (name "unconnected-(U2-PSCK1-Pad14)") (class "Default")
      (node (ref "U2") (pin "14") (pinfunction "PSCK1_14") (pintype "input"))
    )
    (net (code "152") (name "unconnected-(U2-SCKO-Pad4)") (class "Default")
      (node (ref "U2") (pin "4") (pinfunction "SCKO_4") (pintype "output"))
    )
    (net (code "153") (name "unconnected-(U2-UOUT-Pad16)") (class "Default")
      (node (ref "U2") (pin "16") (pinfunction "UOUT_16") (pintype "output"))
    )
    (net (code "154") (name "unconnected-(U2-XTO-Pad7)") (class "Default")
      (node (ref "U2") (pin "7") (pinfunction "XTO_7") (pintype "output"))
    )
    (net (code "155") (name "unconnected-(U3-A0-Pad1)") (class "Default")
      (node (ref "U3") (pin "1") (pinfunction "A0_1") (pintype "input"))
    )
    (net (code "156") (name "unconnected-(U3-A1-Pad2)") (class "Default")
      (node (ref "U3") (pin "2") (pinfunction "A1_2") (pintype "input"))
    )
    (net (code "157") (name "unconnected-(U3-WP-Pad7)") (class "Default")
      (node (ref "U3") (pin "7") (pinfunction "WP_7") (pintype "input"))
    )
  )
)
